# ProPrj_cheap-board-max-10_2026-05-07.net
KiCad netlist of a schematic drawn in EasyEDA Pro
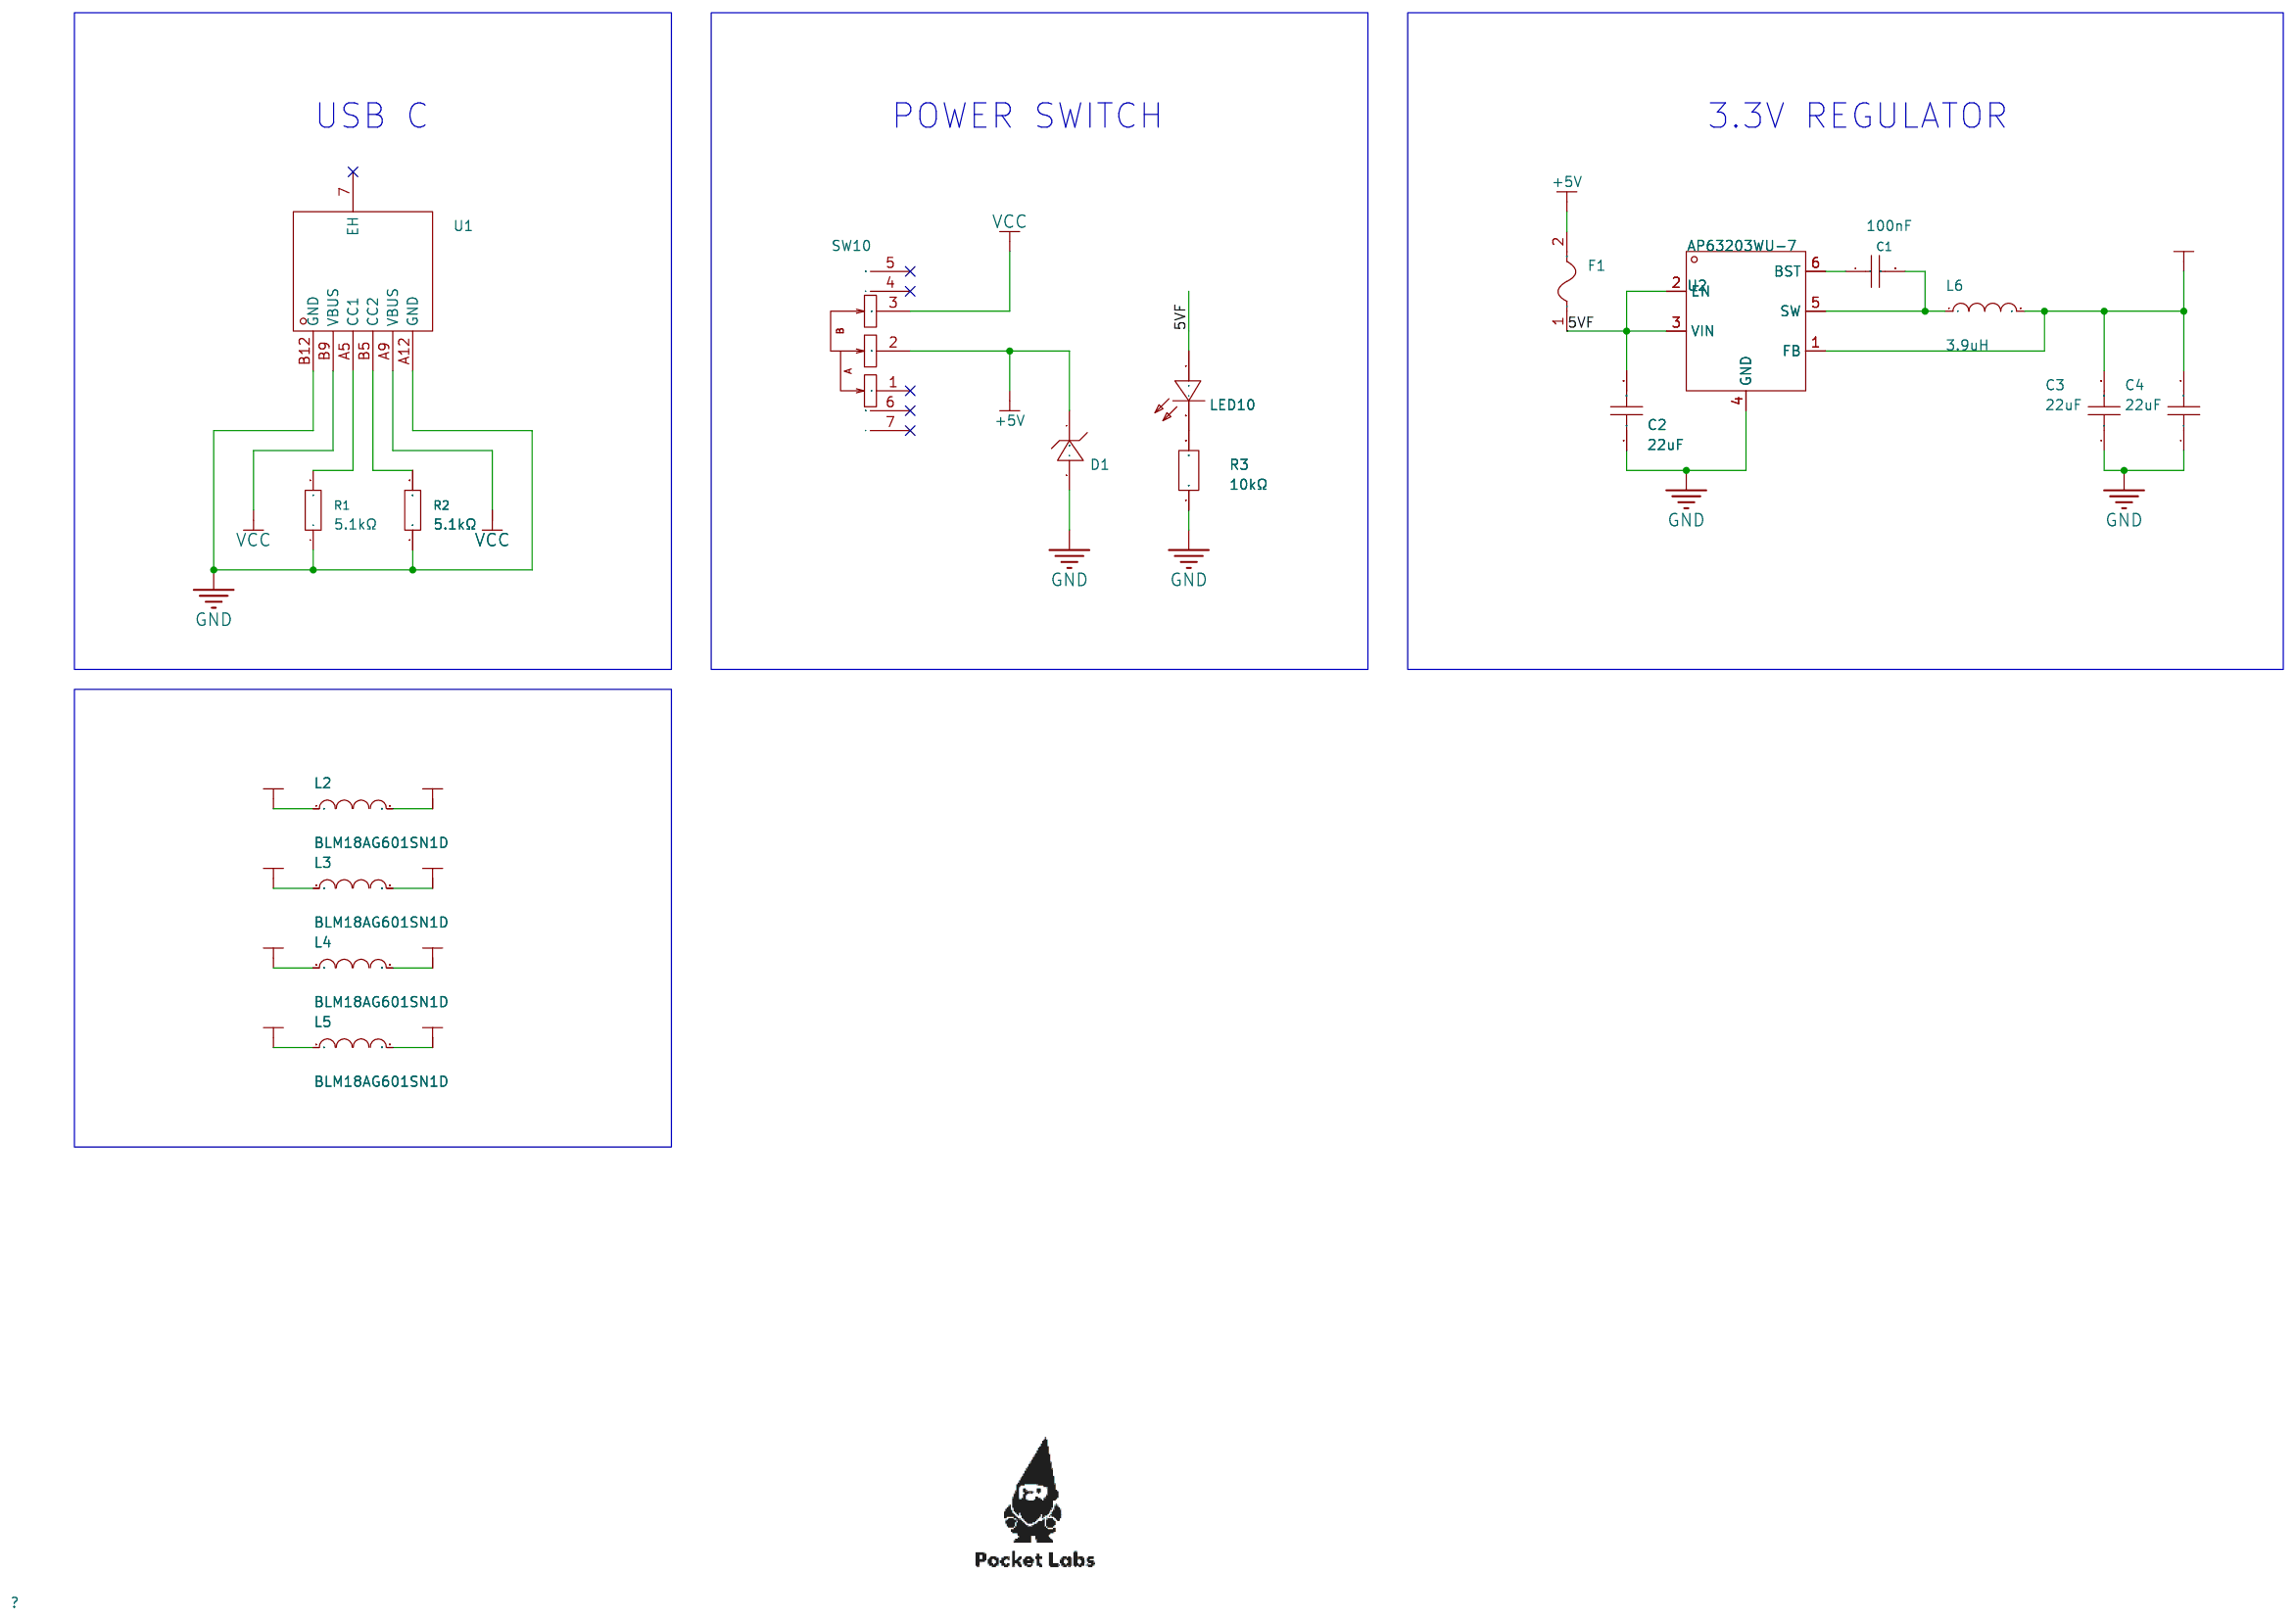
[diagram p0: PWR]
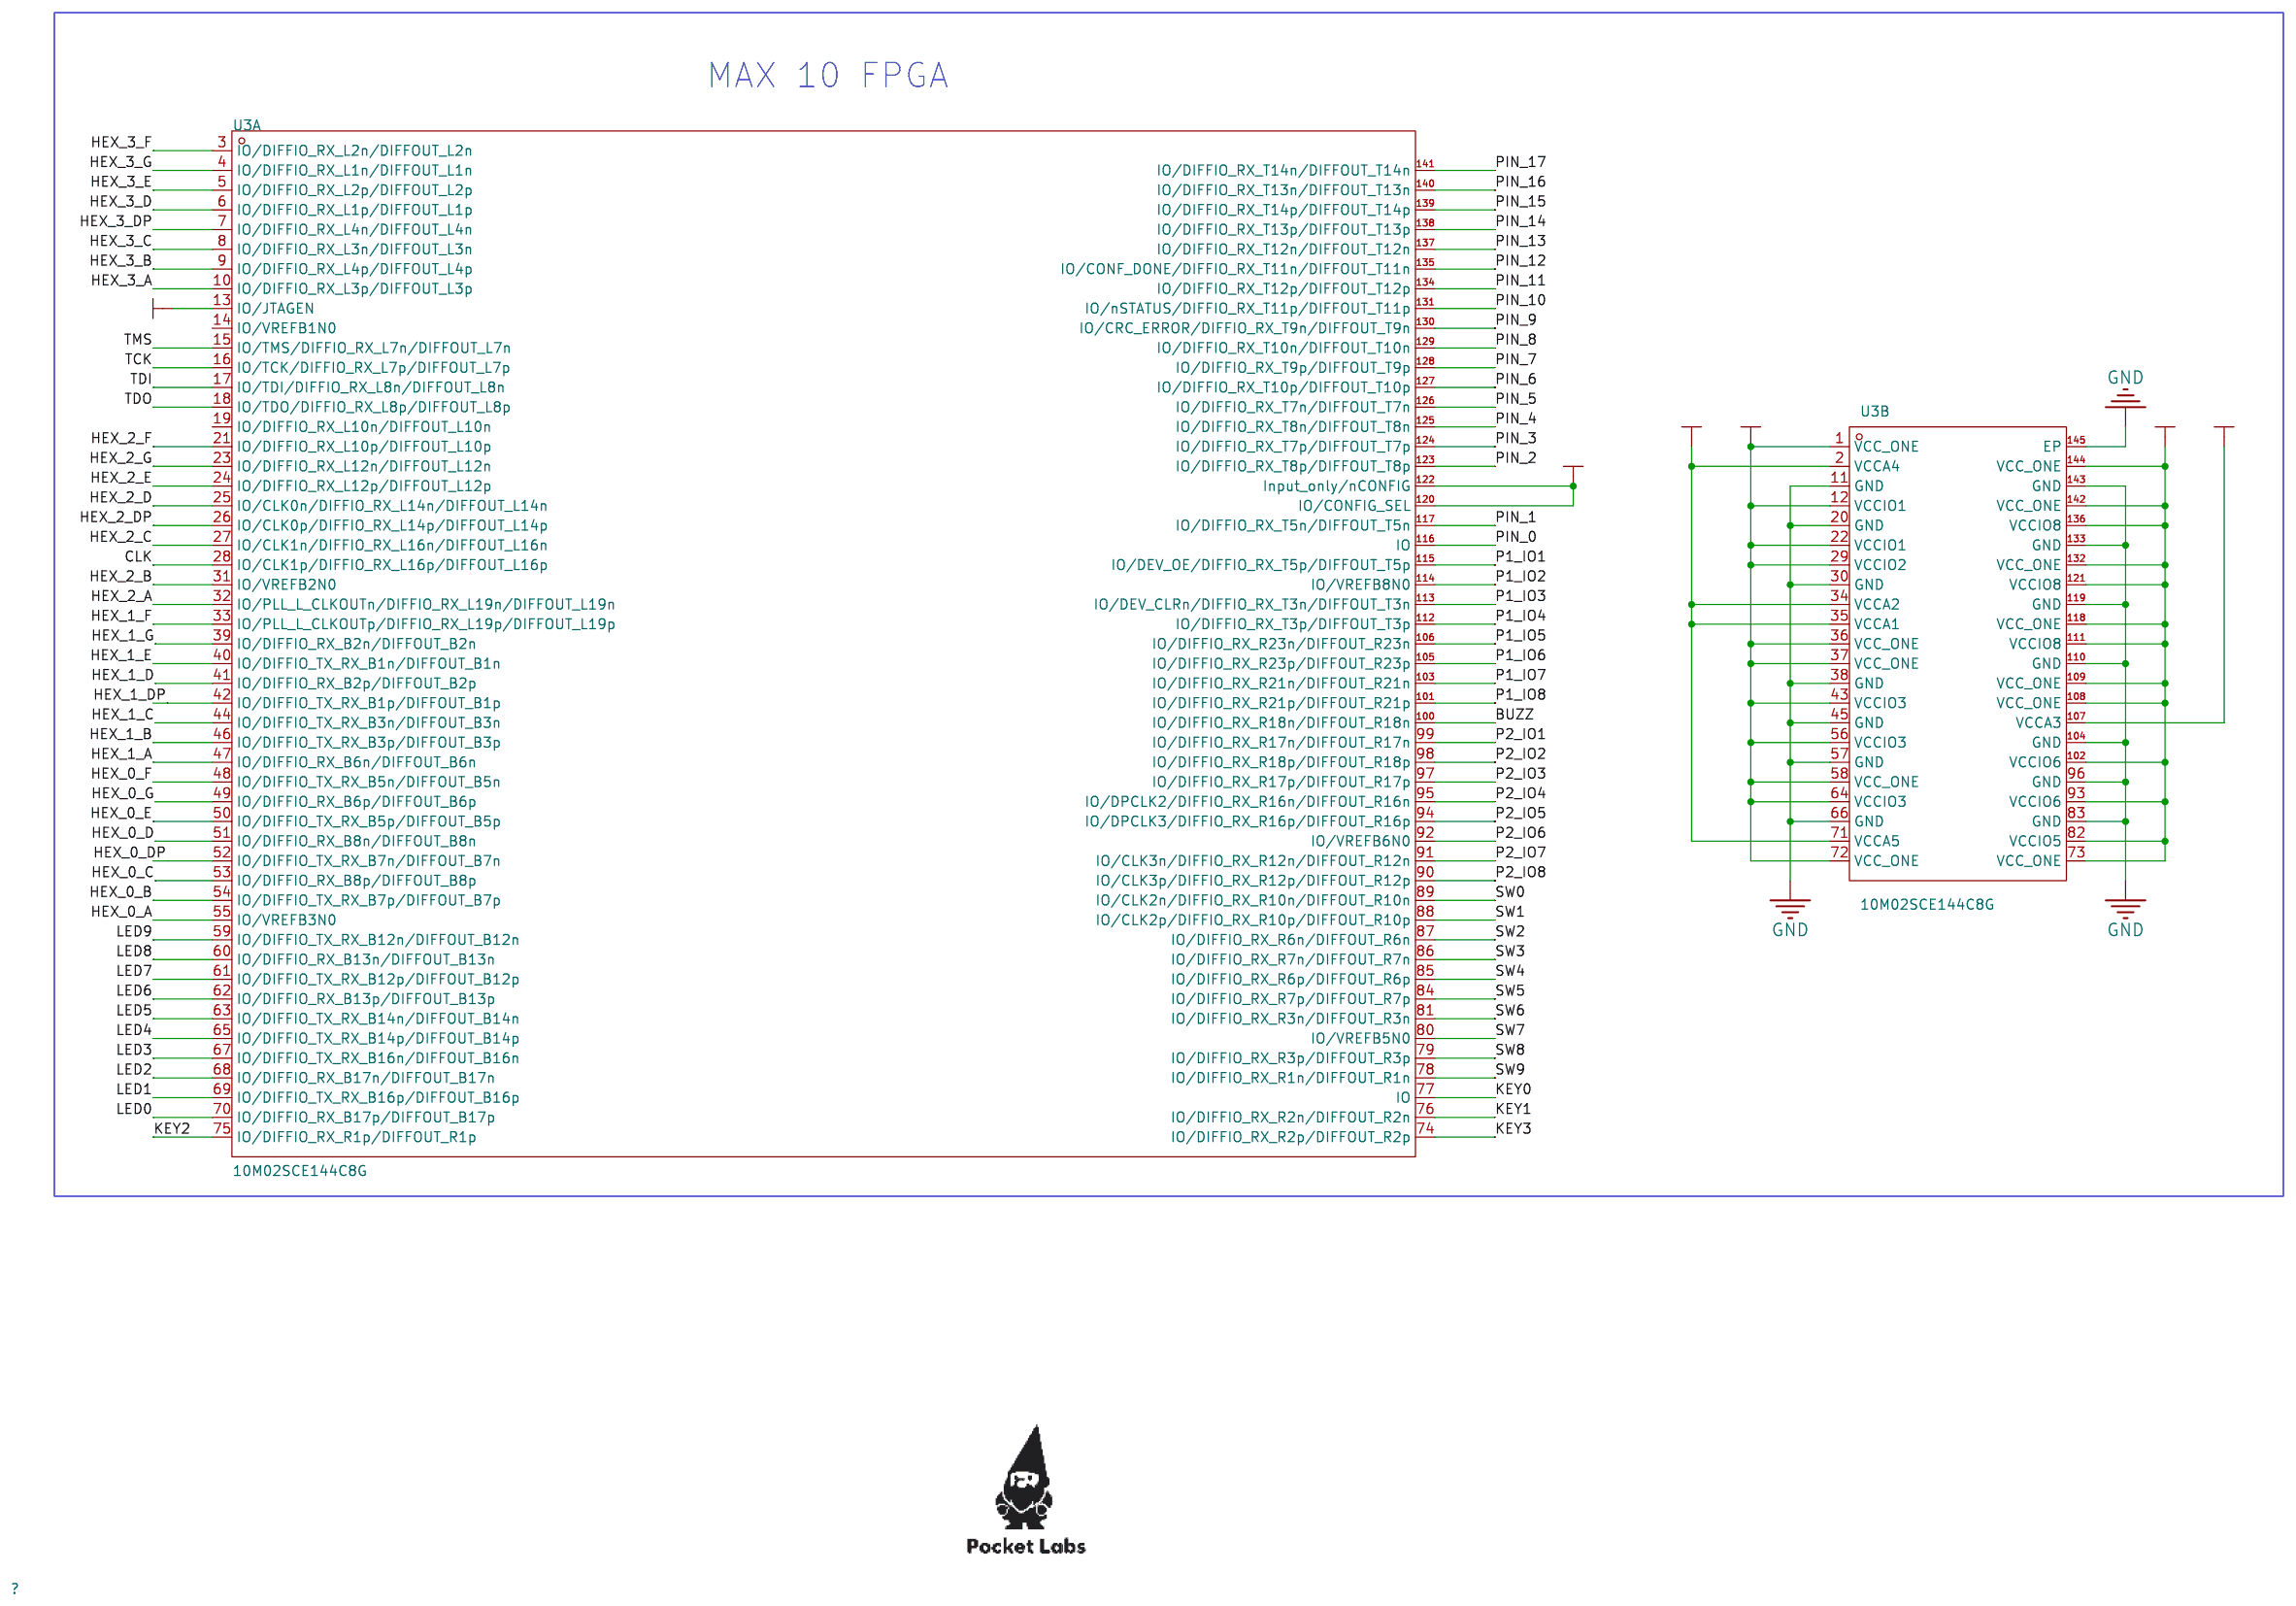
[diagram p1: MAX 10]
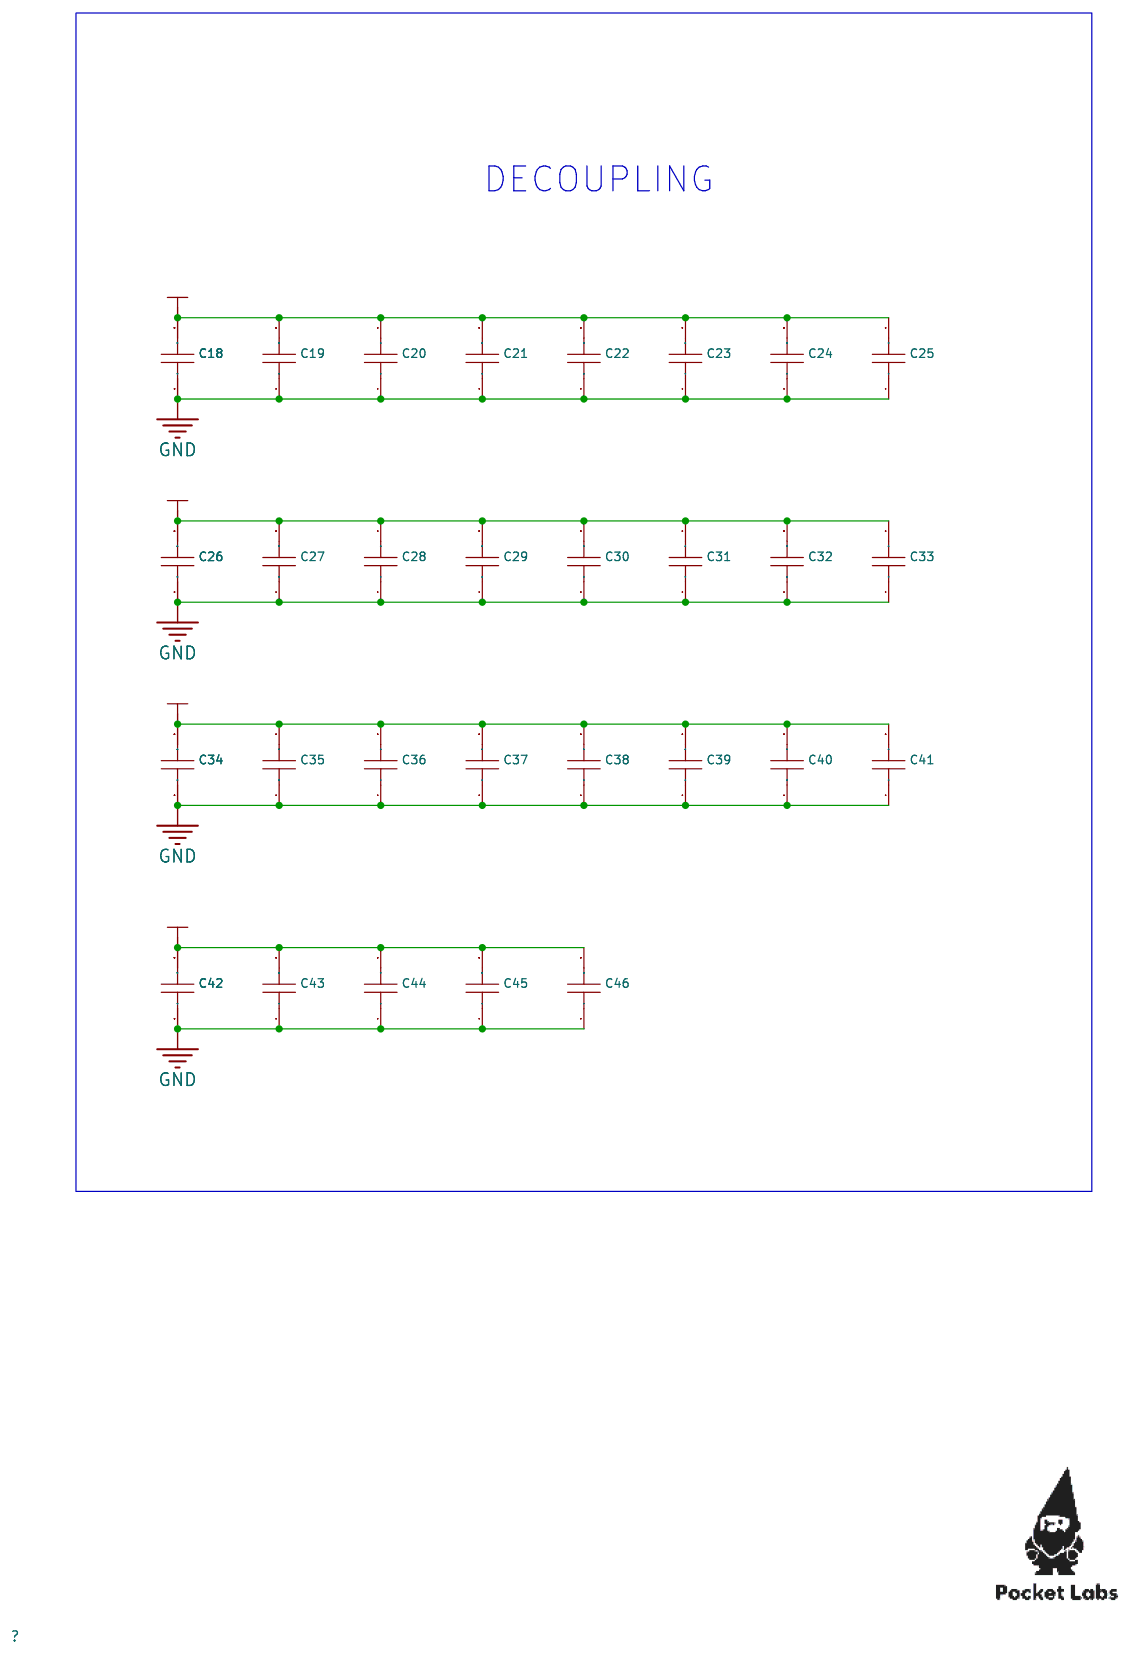
[diagram p2: DEC]
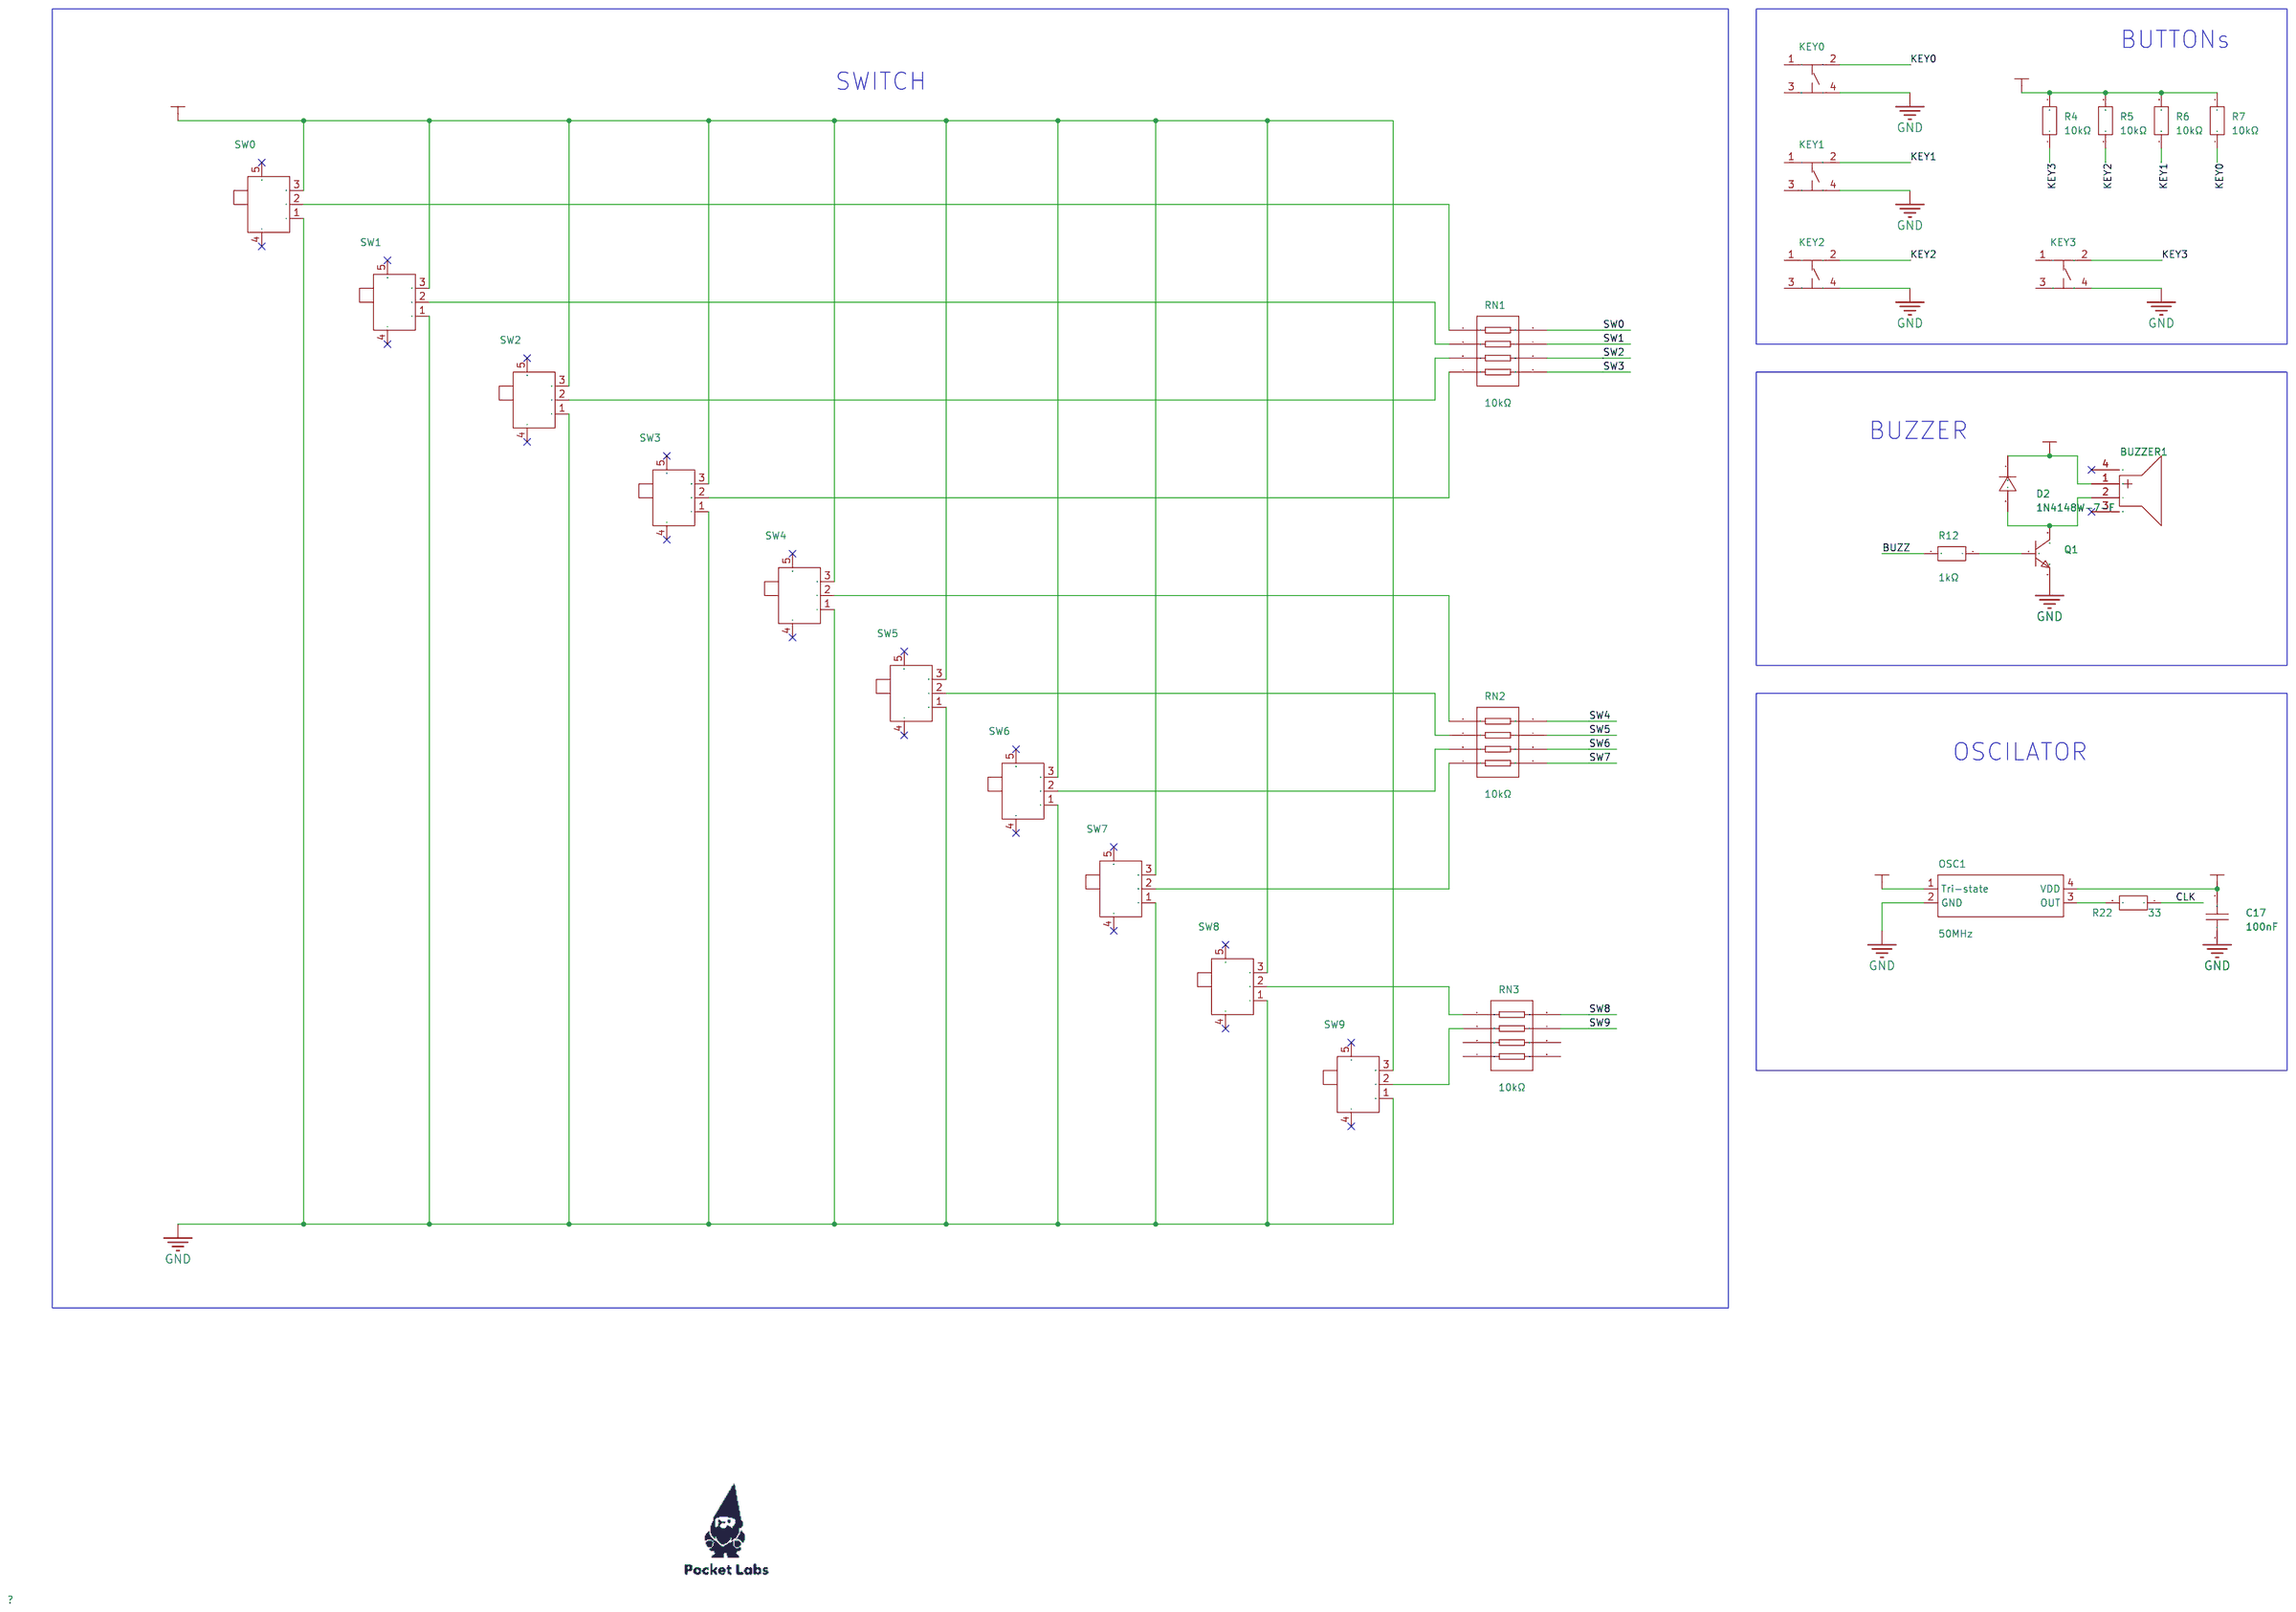
[diagram p3: PERIPHERALS]
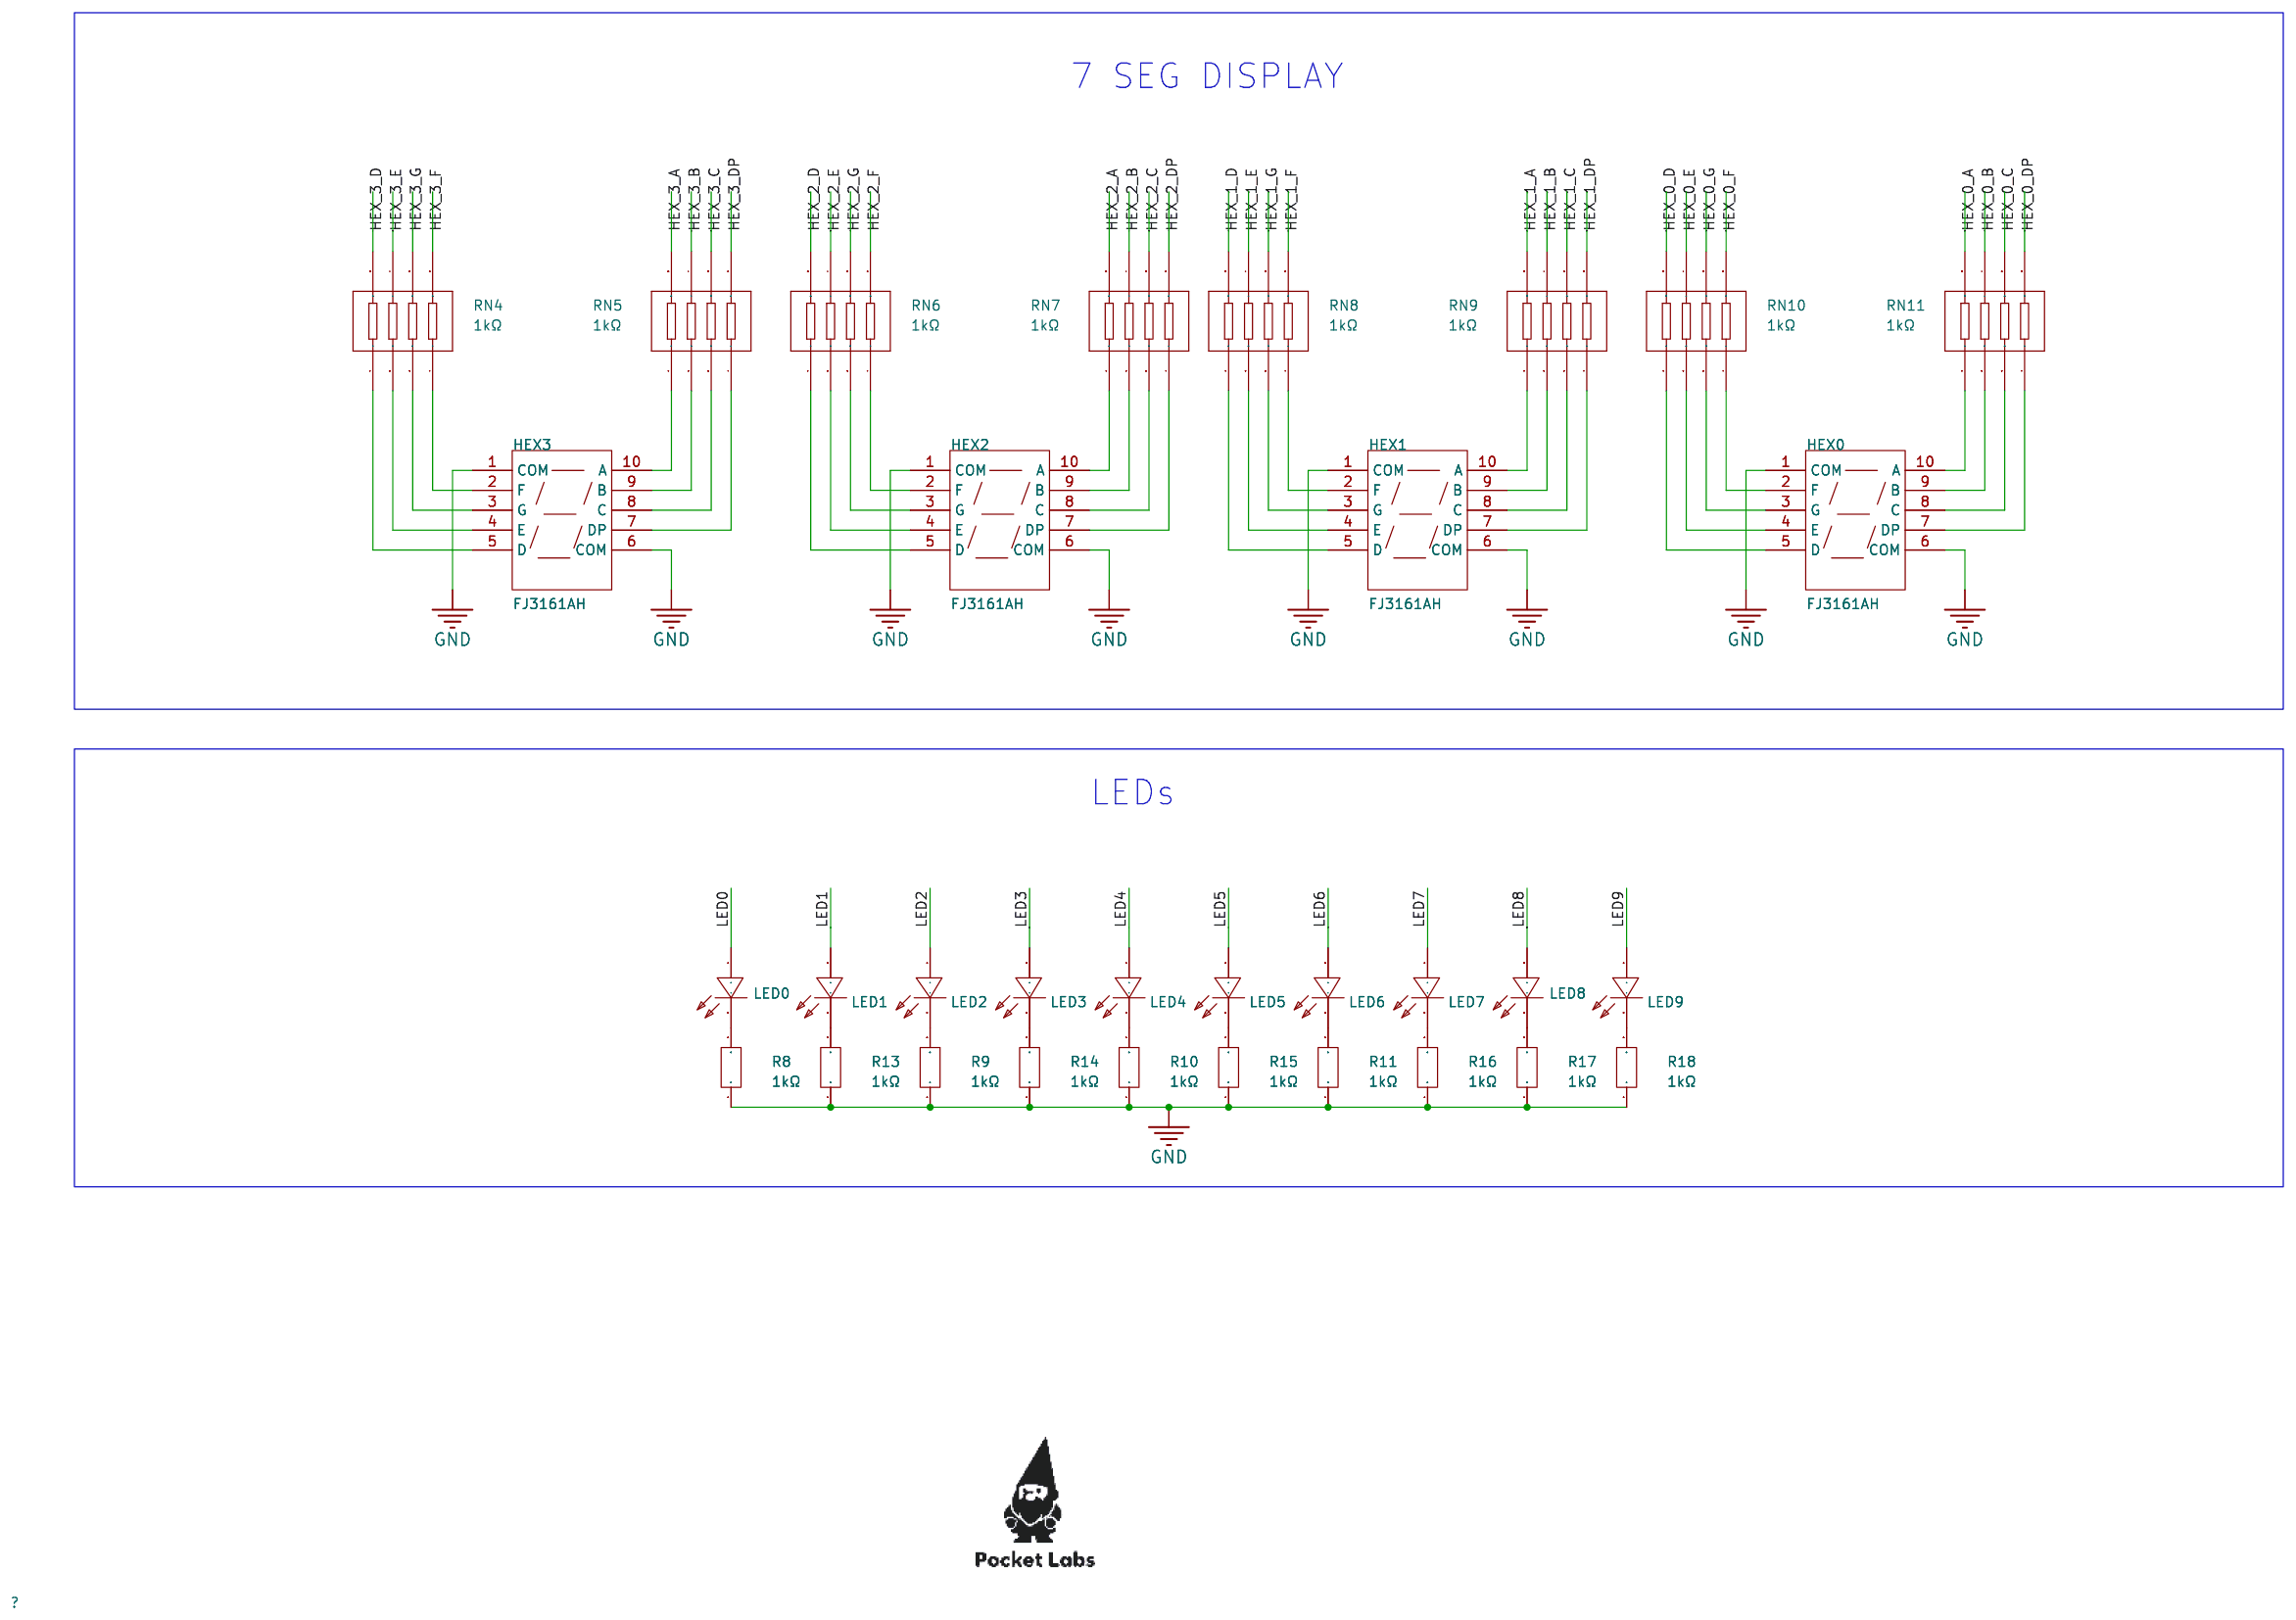
[diagram p4: LEDs]
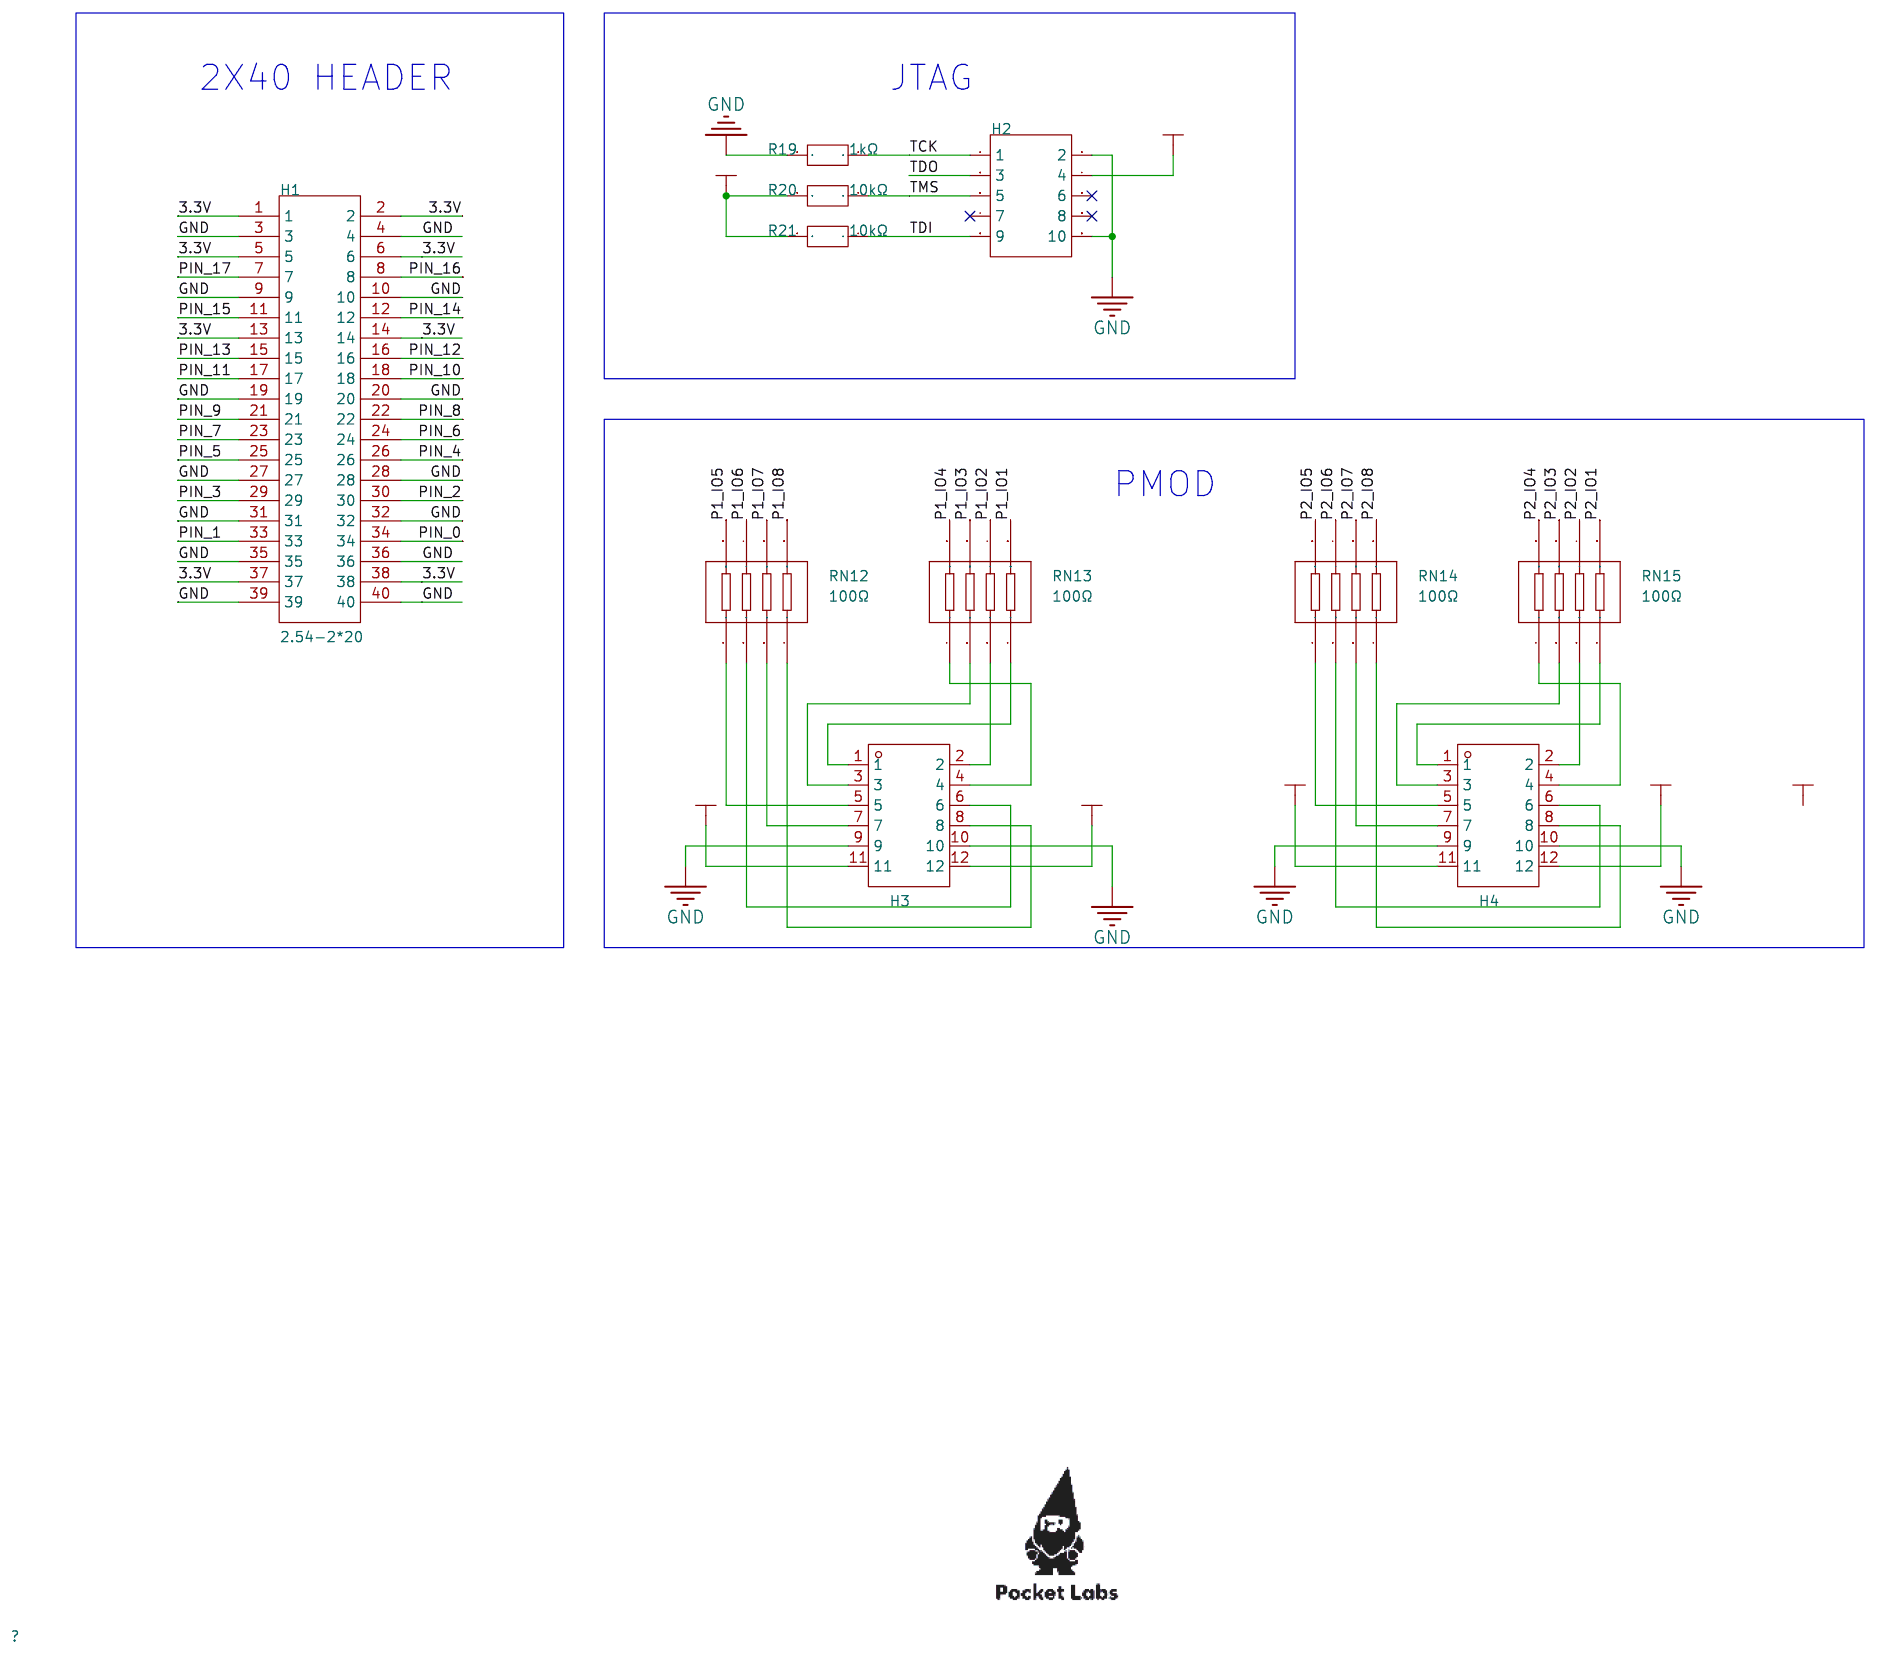
[diagram p5: CONN]

(export (version "E")
  (design (tool "Eeschema 10.0.6"))
  (components
    (comp (ref "C1")
      (value "100nF")
      (footprint "easyedapro:C0603")
      (description "Capacitance:100nF Tolerance:±10% Tolerance:±10% Voltage Rating:16V Temperature Coefficient:X7R")
      (fields
        (field (name "Manufacturer Part") "CL10B104KO8NNNC")
        (field (name "Manufacturer") "SAMSUNG(三星)")
      )
      (libsource (lib "easyedapro") (part "CL10B104KO8NNNC"))
    )
    (comp (ref "C2")
      (value "22uF")
      (footprint "easyedapro:C1206")
      (description "Capacitance:22uF Tolerance:±10% Tolerance:±10% Voltage Rating:16V Temperature Coefficient:X5R")
      (fields
        (field (name "Manufacturer Part") "CL31A226KOHNNNE")
        (field (name "Manufacturer") "SAMSUNG(三星)")
      )
      (libsource (lib "easyedapro") (part "CL31A226KOHNNNE"))
    )
    (comp (ref "C3")
      (value "22uF")
      (footprint "easyedapro:C1206")
      (description "Capacitance:22uF Tolerance:±10% Tolerance:±10% Voltage Rating:16V Temperature Coefficient:X5R")
      (fields
        (field (name "Manufacturer Part") "CL31A226KOHNNNE")
        (field (name "Manufacturer") "SAMSUNG(三星)")
      )
      (libsource (lib "easyedapro") (part "CL31A226KOHNNNE"))
    )
    (comp (ref "C4")
      (value "22uF")
      (footprint "easyedapro:C1206")
      (description "Capacitance:22uF Tolerance:±10% Tolerance:±10% Voltage Rating:16V Temperature Coefficient:X5R")
      (fields
        (field (name "Manufacturer Part") "CL31A226KOHNNNE")
        (field (name "Manufacturer") "SAMSUNG(三星)")
      )
      (libsource (lib "easyedapro") (part "CL31A226KOHNNNE"))
    )
    (comp (ref "D1")
      (value "SMF5.0A")
      (footprint "easyedapro:SOD-123FL_L2.7-W1.8-LS3.8-RD")
      (fields (field (name "Manufacturer") "MDD(辰达半导体)"))
      (libsource (lib "easyedapro") (part "SMF5.0A_C193402"))
    )
    (comp (ref "F1")
      (value "MF-MSMF050-2")
      (footprint "easyedapro:F1812")
      (fields (field (name "Manufacturer") "BOURNS"))
      (libsource (lib "easyedapro") (part "MF-MSMF050-2"))
    )
    (comp (ref "L2")
      (value "BLM18AG601SN1D")
      (footprint "easyedapro:L0603")
      (fields (field (name "Manufacturer") "muRata(村田)"))
      (libsource (lib "easyedapro") (part "BLM18AG601SN1D"))
    )
    (comp (ref "L3")
      (value "BLM18AG601SN1D")
      (footprint "easyedapro:L0603")
      (fields (field (name "Manufacturer") "muRata(村田)"))
      (libsource (lib "easyedapro") (part "BLM18AG601SN1D"))
    )
    (comp (ref "L4")
      (value "BLM18AG601SN1D")
      (footprint "easyedapro:L0603")
      (fields (field (name "Manufacturer") "muRata(村田)"))
      (libsource (lib "easyedapro") (part "BLM18AG601SN1D"))
    )
    (comp (ref "L5")
      (value "BLM18AG601SN1D")
      (footprint "easyedapro:L0603")
      (fields (field (name "Manufacturer") "muRata(村田)"))
      (libsource (lib "easyedapro") (part "BLM18AG601SN1D"))
    )
    (comp (ref "L6")
      (value "3.9uH")
      (footprint "easyedapro:IND-SMD_TNR4030S-3R9MTF")
      (fields (field (name "Manufacturer Part") "TNR4030S-3R9MTF") (field (name "Manufacturer") "APV(爱普微)"))
      (libsource (lib "easyedapro") (part "TNR4030S-3R9MTF"))
    )
    (comp (ref "LED10")
      (value "YLED0603R")
      (footprint "easyedapro:LED0805-R-RD")
      (fields (field (name "Manufacturer") "YONGYUTAI(永裕泰)"))
      (libsource (lib "easyedapro") (part "FC-2012HRK-620D"))
    )
    (comp (ref "R1")
      (value "5.1kΩ")
      (footprint "easyedapro:R0603")
      (fields (field (name "Manufacturer Part") "RMC06035.1K1%N") (field (name "Manufacturer") "Tyohm(幸亚电阻)"))
      (libsource (lib "easyedapro") (part "RMC06035.1K1%N"))
    )
    (comp (ref "R2")
      (value "5.1kΩ")
      (footprint "easyedapro:R0603")
      (fields (field (name "Manufacturer Part") "RMC06035.1K1%N") (field (name "Manufacturer") "Tyohm(幸亚电阻)"))
      (libsource (lib "easyedapro") (part "RMC06035.1K1%N"))
    )
    (comp (ref "R3")
      (value "10kΩ")
      (fields (field (name "Manufacturer Part") "RC0603FR-071KL") (field (name "Manufacturer") "YAGEO(国巨)"))
      (libsource (lib "easyedapro") (part "SC1206J1500F8ANRH"))
    )
    (comp (ref "SW10")
      (value "MK-12C02-G020")
      (fields (field (name "Manufacturer") "G-Switch(品赞)"))
      (libsource (lib "easyedapro") (part "MK-12C02-G015"))
    )
    (comp (ref "U1")
      (value "USB-TYPE-C-009")
      (footprint "easyedapro:TYPE-C-SMD_TYPE-C-6P")
      (fields (field (name "Manufacturer") "DEALON(德艺隆)"))
      (libsource (lib "easyedapro") (part "USB-TYPE-C-009"))
    )
    (comp (ref "U2")
      (value "AP63203WU-7")
      (footprint "easyedapro:TSOT-26_L2.9-W1.6-P0.95-LS2.8-BL")
      (fields (field (name "Manufacturer") "DIODES(美台)"))
      (libsource (lib "easyedapro") (part "AP63203WU-7"))
    )
    (comp (ref "U3")
      (value "10M02SCE144C8G")
      (footprint "easyedapro:EQFP-144_L20.0-W20.0-P0.50-LS22.0-BL-EP4.0")
      (fields (field (name "Manufacturer") "Intel/Altera"))
      (libsource (lib "easyedapro") (part "10M02SCE144C8G"))
    )
    (comp (ref "C18")
      (value "100nF")
      (footprint "easyedapro:C0402")
      (fields
        (field (name "Manufacturer Part") "CC0402KRX7R7BB104")
        (field (name "Manufacturer") "YAGEO(国巨)")
      )
      (libsource (lib "easyedapro") (part "CC0402KRX7R7BB104"))
    )
    (comp (ref "C19")
      (value "100nF")
      (footprint "easyedapro:C0402")
      (fields
        (field (name "Manufacturer Part") "CC0402KRX7R7BB104")
        (field (name "Manufacturer") "YAGEO(国巨)")
      )
      (libsource (lib "easyedapro") (part "CC0402KRX7R7BB104"))
    )
    (comp (ref "C20")
      (value "100nF")
      (footprint "easyedapro:C0402")
      (fields
        (field (name "Manufacturer Part") "CC0402KRX7R7BB104")
        (field (name "Manufacturer") "YAGEO(国巨)")
      )
      (libsource (lib "easyedapro") (part "CC0402KRX7R7BB104"))
    )
    (comp (ref "C21")
      (value "100nF")
      (footprint "easyedapro:C0402")
      (fields
        (field (name "Manufacturer Part") "CC0402KRX7R7BB104")
        (field (name "Manufacturer") "YAGEO(国巨)")
      )
      (libsource (lib "easyedapro") (part "CC0402KRX7R7BB104"))
    )
    (comp (ref "C22")
      (value "100nF")
      (footprint "easyedapro:C0402")
      (fields
        (field (name "Manufacturer Part") "CC0402KRX7R7BB104")
        (field (name "Manufacturer") "YAGEO(国巨)")
      )
      (libsource (lib "easyedapro") (part "CC0402KRX7R7BB104"))
    )
    (comp (ref "C23")
      (value "100nF")
      (footprint "easyedapro:C0402")
      (fields
        (field (name "Manufacturer Part") "CC0402KRX7R7BB104")
        (field (name "Manufacturer") "YAGEO(国巨)")
      )
      (libsource (lib "easyedapro") (part "CC0402KRX7R7BB104"))
    )
    (comp (ref "C24")
      (value "100nF")
      (footprint "easyedapro:C0402")
      (fields
        (field (name "Manufacturer Part") "CC0402KRX7R7BB104")
        (field (name "Manufacturer") "YAGEO(国巨)")
      )
      (libsource (lib "easyedapro") (part "CC0402KRX7R7BB104"))
    )
    (comp (ref "C25")
      (value "100nF")
      (footprint "easyedapro:C0402")
      (fields
        (field (name "Manufacturer Part") "CC0402KRX7R7BB104")
        (field (name "Manufacturer") "YAGEO(国巨)")
      )
      (libsource (lib "easyedapro") (part "CC0402KRX7R7BB104"))
    )
    (comp (ref "C26")
      (value "100nF")
      (footprint "easyedapro:C0402")
      (fields
        (field (name "Manufacturer Part") "CC0402KRX7R7BB104")
        (field (name "Manufacturer") "YAGEO(国巨)")
      )
      (libsource (lib "easyedapro") (part "CC0402KRX7R7BB104"))
    )
    (comp (ref "C27")
      (value "100nF")
      (footprint "easyedapro:C0402")
      (fields
        (field (name "Manufacturer Part") "CC0402KRX7R7BB104")
        (field (name "Manufacturer") "YAGEO(国巨)")
      )
      (libsource (lib "easyedapro") (part "CC0402KRX7R7BB104"))
    )
    (comp (ref "C28")
      (value "100nF")
      (footprint "easyedapro:C0402")
      (fields
        (field (name "Manufacturer Part") "CC0402KRX7R7BB104")
        (field (name "Manufacturer") "YAGEO(国巨)")
      )
      (libsource (lib "easyedapro") (part "CC0402KRX7R7BB104"))
    )
    (comp (ref "C29")
      (value "100nF")
      (footprint "easyedapro:C0402")
      (fields
        (field (name "Manufacturer Part") "CC0402KRX7R7BB104")
        (field (name "Manufacturer") "YAGEO(国巨)")
      )
      (libsource (lib "easyedapro") (part "CC0402KRX7R7BB104"))
    )
    (comp (ref "C30")
      (value "100nF")
      (footprint "easyedapro:C0402")
      (fields
        (field (name "Manufacturer Part") "CC0402KRX7R7BB104")
        (field (name "Manufacturer") "YAGEO(国巨)")
      )
      (libsource (lib "easyedapro") (part "CC0402KRX7R7BB104"))
    )
    (comp (ref "C31")
      (value "100nF")
      (footprint "easyedapro:C0402")
      (fields
        (field (name "Manufacturer Part") "CC0402KRX7R7BB104")
        (field (name "Manufacturer") "YAGEO(国巨)")
      )
      (libsource (lib "easyedapro") (part "CC0402KRX7R7BB104"))
    )
    (comp (ref "C32")
      (value "100nF")
      (footprint "easyedapro:C0402")
      (fields
        (field (name "Manufacturer Part") "CC0402KRX7R7BB104")
        (field (name "Manufacturer") "YAGEO(国巨)")
      )
      (libsource (lib "easyedapro") (part "CC0402KRX7R7BB104"))
    )
    (comp (ref "C33")
      (value "100nF")
      (footprint "easyedapro:C0402")
      (fields
        (field (name "Manufacturer Part") "CC0402KRX7R7BB104")
        (field (name "Manufacturer") "YAGEO(国巨)")
      )
      (libsource (lib "easyedapro") (part "CC0402KRX7R7BB104"))
    )
    (comp (ref "C34")
      (value "100nF")
      (footprint "easyedapro:C0402")
      (fields
        (field (name "Manufacturer Part") "CC0402KRX7R7BB104")
        (field (name "Manufacturer") "YAGEO(国巨)")
      )
      (libsource (lib "easyedapro") (part "CC0402KRX7R7BB104"))
    )
    (comp (ref "C35")
      (value "100nF")
      (footprint "easyedapro:C0402")
      (fields
        (field (name "Manufacturer Part") "CC0402KRX7R7BB104")
        (field (name "Manufacturer") "YAGEO(国巨)")
      )
      (libsource (lib "easyedapro") (part "CC0402KRX7R7BB104"))
    )
    (comp (ref "C36")
      (value "100nF")
      (footprint "easyedapro:C0402")
      (fields
        (field (name "Manufacturer Part") "CC0402KRX7R7BB104")
        (field (name "Manufacturer") "YAGEO(国巨)")
      )
      (libsource (lib "easyedapro") (part "CC0402KRX7R7BB104"))
    )
    (comp (ref "C37")
      (value "100nF")
      (footprint "easyedapro:C0402")
      (fields
        (field (name "Manufacturer Part") "CC0402KRX7R7BB104")
        (field (name "Manufacturer") "YAGEO(国巨)")
      )
      (libsource (lib "easyedapro") (part "CC0402KRX7R7BB104"))
    )
    (comp (ref "C38")
      (value "100nF")
      (footprint "easyedapro:C0402")
      (fields
        (field (name "Manufacturer Part") "CC0402KRX7R7BB104")
        (field (name "Manufacturer") "YAGEO(国巨)")
      )
      (libsource (lib "easyedapro") (part "CC0402KRX7R7BB104"))
    )
    (comp (ref "C39")
      (value "100nF")
      (footprint "easyedapro:C0402")
      (fields
        (field (name "Manufacturer Part") "CC0402KRX7R7BB104")
        (field (name "Manufacturer") "YAGEO(国巨)")
      )
      (libsource (lib "easyedapro") (part "CC0402KRX7R7BB104"))
    )
    (comp (ref "C40")
      (value "100nF")
      (footprint "easyedapro:C0402")
      (fields
        (field (name "Manufacturer Part") "CC0402KRX7R7BB104")
        (field (name "Manufacturer") "YAGEO(国巨)")
      )
      (libsource (lib "easyedapro") (part "CC0402KRX7R7BB104"))
    )
    (comp (ref "C41")
      (value "100nF")
      (footprint "easyedapro:C0402")
      (fields
        (field (name "Manufacturer Part") "CC0402KRX7R7BB104")
        (field (name "Manufacturer") "YAGEO(国巨)")
      )
      (libsource (lib "easyedapro") (part "CC0402KRX7R7BB104"))
    )
    (comp (ref "C42")
      (value "100nF")
      (footprint "easyedapro:C0402")
      (fields
        (field (name "Manufacturer Part") "CC0402KRX7R7BB104")
        (field (name "Manufacturer") "YAGEO(国巨)")
      )
      (libsource (lib "easyedapro") (part "CC0402KRX7R7BB104"))
    )
    (comp (ref "C43")
      (value "100nF")
      (footprint "easyedapro:C0402")
      (fields
        (field (name "Manufacturer Part") "CC0402KRX7R7BB104")
        (field (name "Manufacturer") "YAGEO(国巨)")
      )
      (libsource (lib "easyedapro") (part "CC0402KRX7R7BB104"))
    )
    (comp (ref "C44")
      (value "100nF")
      (footprint "easyedapro:C0402")
      (fields
        (field (name "Manufacturer Part") "CC0402KRX7R7BB104")
        (field (name "Manufacturer") "YAGEO(国巨)")
      )
      (libsource (lib "easyedapro") (part "CC0402KRX7R7BB104"))
    )
    (comp (ref "C45")
      (value "100nF")
      (footprint "easyedapro:C0402")
      (fields
        (field (name "Manufacturer Part") "CC0402KRX7R7BB104")
        (field (name "Manufacturer") "YAGEO(国巨)")
      )
      (libsource (lib "easyedapro") (part "CC0402KRX7R7BB104"))
    )
    (comp (ref "C46")
      (value "100nF")
      (footprint "easyedapro:C0402")
      (fields
        (field (name "Manufacturer Part") "CC0402KRX7R7BB104")
        (field (name "Manufacturer") "YAGEO(国巨)")
      )
      (libsource (lib "easyedapro") (part "CC0402KRX7R7BB104"))
    )
    (comp (ref "BUZZER1")
      (value "2.7kHz")
      (footprint "easyedapro:BUZ-SMD_4P-L7.5-W7.5-P7.59-TL")
      (fields (field (name "Manufacturer Part") "MLT-7525") (field (name "Manufacturer") "华能"))
      (libsource (lib "easyedapro") (part "MLT-7525"))
    )
    (comp (ref "C17")
      (value "100nF")
      (footprint "easyedapro:C0603")
      (description "Capacitance:100nF Tolerance:±10% Tolerance:±10% Voltage Rating:50V Temperature Coefficient:X7R")
      (fields
        (field (name "Manufacturer Part") "CC0603KRX7R9BB104")
        (field (name "Manufacturer") "YAGEO(国巨)")
      )
      (libsource (lib "easyedapro") (part "CC0603KRX7R9BB104"))
    )
    (comp (ref "D2")
      (value "1N4148W-7-F")
      (footprint "easyedapro:SOD-123_L2.7-W1.6-LS3.7-RD-1")
      (fields (field (name "Manufacturer") "DIODES(美台)"))
      (libsource (lib "easyedapro") (part "1N4148W-7-F"))
    )
    (comp (ref "KEY0")
      (value "KH-6X6X6H-STM")
      (footprint "easyedapro:SW-SMD_4P-L6.0-W6.0-P4.50-LS9.0_KH-6X6X6H-STM")
      (fields (field (name "Manufacturer") "kinghelm(金航标)"))
      (libsource (lib "easyedapro") (part "KH-6X6X6H-STM"))
    )
    (comp (ref "KEY1")
      (value "KH-6X6X6H-STM")
      (footprint "easyedapro:SW-SMD_4P-L6.0-W6.0-P4.50-LS9.0_KH-6X6X6H-STM")
      (fields (field (name "Manufacturer") "kinghelm(金航标)"))
      (libsource (lib "easyedapro") (part "KH-6X6X6H-STM"))
    )
    (comp (ref "KEY2")
      (value "KH-6X6X6H-STM")
      (footprint "easyedapro:SW-SMD_4P-L6.0-W6.0-P4.50-LS9.0_KH-6X6X6H-STM")
      (fields (field (name "Manufacturer") "kinghelm(金航标)"))
      (libsource (lib "easyedapro") (part "KH-6X6X6H-STM"))
    )
    (comp (ref "KEY3")
      (value "KH-6X6X6H-STM")
      (footprint "easyedapro:SW-SMD_4P-L6.0-W6.0-P4.50-LS9.0_KH-6X6X6H-STM")
      (fields (field (name "Manufacturer") "kinghelm(金航标)"))
      (libsource (lib "easyedapro") (part "KH-6X6X6H-STM"))
    )
    (comp (ref "OSC1")
      (value "50MHz")
      (footprint "easyedapro:OSC-SMD_4P-L3.2-W2.5-BL")
      (fields
        (field (name "Manufacturer Part") "OT2EL4C4JI-111OLP-50M")
        (field (name "Manufacturer") "YXC(扬兴晶振)")
      )
      (libsource (lib "easyedapro") (part "OT2EL4C4JI-111OLP-50M"))
    )
    (comp (ref "Q1")
      (value "MMBT3904LT1G")
      (footprint "easyedapro:SOT-23-3_L2.9-W1.6-P1.90-LS2.8-BR")
      (fields (field (name "Manufacturer") "onsemi(安森美)"))
      (libsource (lib "easyedapro") (part "MMBT3904LT1G"))
    )
    (comp (ref "R4")
      (value "10kΩ")
      (fields (field (name "Manufacturer Part") "RC0603FR-071KL") (field (name "Manufacturer") "YAGEO(国巨)"))
      (libsource (lib "easyedapro") (part "SC1206J1500F8ANRH"))
    )
    (comp (ref "R5")
      (value "10kΩ")
      (fields (field (name "Manufacturer Part") "RC0603FR-071KL") (field (name "Manufacturer") "YAGEO(国巨)"))
      (libsource (lib "easyedapro") (part "SC1206J1500F8ANRH"))
    )
    (comp (ref "R6")
      (value "10kΩ")
      (fields (field (name "Manufacturer Part") "RC0603FR-071KL") (field (name "Manufacturer") "YAGEO(国巨)"))
      (libsource (lib "easyedapro") (part "SC1206J1500F8ANRH"))
    )
    (comp (ref "R7")
      (value "10kΩ")
      (fields (field (name "Manufacturer Part") "RC0603FR-071KL") (field (name "Manufacturer") "YAGEO(国巨)"))
      (libsource (lib "easyedapro") (part "SC1206J1500F8ANRH"))
    )
    (comp (ref "R12")
      (value "1kΩ")
      (fields (field (name "Manufacturer Part") "RC0603FR-071KL") (field (name "Manufacturer") "YAGEO(国巨)"))
      (libsource (lib "easyedapro") (part "SC1206J1500F8ANRH"))
    )
    (comp (ref "R22")
      (value "33")
      (fields (field (name "Manufacturer Part") "RC0603FR-071KL") (field (name "Manufacturer") "YAGEO(国巨)"))
      (libsource (lib "easyedapro") (part "SC1206J1500F8ANRH"))
    )
    (comp (ref "RN1")
      (value "10kΩ")
      (footprint "easyedapro:RES-ARRAY-SMD_0603-8P-L3.2-W1.6-BL")
      (fields
        (field (name "Manufacturer Part") "4D03WGJ0103T5E")
        (field (name "Manufacturer") "UNI-ROYAL(厚声)")
      )
      (libsource (lib "easyedapro") (part "4D03WGJ0103T5E"))
    )
    (comp (ref "RN2")
      (value "10kΩ")
      (footprint "easyedapro:RES-ARRAY-SMD_0603-8P-L3.2-W1.6-BL")
      (fields
        (field (name "Manufacturer Part") "4D03WGJ0103T5E")
        (field (name "Manufacturer") "UNI-ROYAL(厚声)")
      )
      (libsource (lib "easyedapro") (part "4D03WGJ0103T5E"))
    )
    (comp (ref "RN3")
      (value "10kΩ")
      (footprint "easyedapro:RES-ARRAY-SMD_0603-8P-L3.2-W1.6-BL")
      (fields
        (field (name "Manufacturer Part") "4D03WGJ0103T5E")
        (field (name "Manufacturer") "UNI-ROYAL(厚声)")
      )
      (libsource (lib "easyedapro") (part "4D03WGJ0103T5E"))
    )
    (comp (ref "SW0")
      (value "SS12F44G4")
      (fields (field (name "Manufacturer") "SHOU HAN(首韩)"))
      (libsource (lib "easyedapro") (part "SS12D07VG4 087"))
    )
    (comp (ref "SW1")
      (value "SS12F44G4")
      (fields (field (name "Manufacturer") "SHOU HAN(首韩)"))
      (libsource (lib "easyedapro") (part "SS12D07VG4 087"))
    )
    (comp (ref "SW2")
      (value "SS12F44G4")
      (fields (field (name "Manufacturer") "SHOU HAN(首韩)"))
      (libsource (lib "easyedapro") (part "SS12D07VG4 087"))
    )
    (comp (ref "SW3")
      (value "SS12F44G4")
      (fields (field (name "Manufacturer") "SHOU HAN(首韩)"))
      (libsource (lib "easyedapro") (part "SS12D07VG4 087"))
    )
    (comp (ref "SW4")
      (value "SS12F44G4")
      (fields (field (name "Manufacturer") "SHOU HAN(首韩)"))
      (libsource (lib "easyedapro") (part "SS12D07VG4 087"))
    )
    (comp (ref "SW5")
      (value "SS12F44G4")
      (fields (field (name "Manufacturer") "SHOU HAN(首韩)"))
      (libsource (lib "easyedapro") (part "SS12D07VG4 087"))
    )
    (comp (ref "SW6")
      (value "SS12F44G4")
      (fields (field (name "Manufacturer") "SHOU HAN(首韩)"))
      (libsource (lib "easyedapro") (part "SS12D07VG4 087"))
    )
    (comp (ref "SW7")
      (value "SS12F44G4")
      (fields (field (name "Manufacturer") "SHOU HAN(首韩)"))
      (libsource (lib "easyedapro") (part "SS12D07VG4 087"))
    )
    (comp (ref "SW8")
      (value "SS12F44G4")
      (fields (field (name "Manufacturer") "SHOU HAN(首韩)"))
      (libsource (lib "easyedapro") (part "SS12D07VG4 087"))
    )
    (comp (ref "SW9")
      (value "SS12F44G4")
      (fields (field (name "Manufacturer") "SHOU HAN(首韩)"))
      (libsource (lib "easyedapro") (part "SS12D07VG4 087"))
    )
    (comp (ref "HEX0")
      (value "FJ3161AH")
      (footprint "easyedapro:LED-SEG-TH_10P-L14.0-W7.5-P2.54-S5.08-TL")
      (description "Digit/Alpha Size(inch):0.36 Illumination Color:Red LED Polarity:Common Cathode")
      (fields (field (name "Manufacturer") "志浩"))
      (libsource (lib "easyedapro") (part "XL-DB3161SRBC"))
    )
    (comp (ref "HEX1")
      (value "FJ3161AH")
      (footprint "easyedapro:LED-SEG-TH_10P-L14.0-W7.5-P2.54-S5.08-TL")
      (description "Digit/Alpha Size(inch):0.36 Illumination Color:Red LED Polarity:Common Cathode")
      (fields (field (name "Manufacturer") "志浩"))
      (libsource (lib "easyedapro") (part "XL-DB3161SRBC"))
    )
    (comp (ref "HEX2")
      (value "FJ3161AH")
      (footprint "easyedapro:LED-SEG-TH_10P-L14.0-W7.5-P2.54-S5.08-TL")
      (description "Digit/Alpha Size(inch):0.36 Illumination Color:Red LED Polarity:Common Cathode")
      (fields (field (name "Manufacturer") "志浩"))
      (libsource (lib "easyedapro") (part "XL-DB3161SRBC"))
    )
    (comp (ref "HEX3")
      (value "FJ3161AH")
      (footprint "easyedapro:LED-SEG-TH_10P-L14.0-W7.5-P2.54-S5.08-TL")
      (description "Digit/Alpha Size(inch):0.36 Illumination Color:Red LED Polarity:Common Cathode")
      (fields (field (name "Manufacturer") "志浩"))
      (libsource (lib "easyedapro") (part "XL-DB3161SRBC"))
    )
    (comp (ref "LED0")
      (value "YLED0603R")
      (footprint "easyedapro:LED0805-R-RD")
      (fields (field (name "Manufacturer") "YONGYUTAI(永裕泰)"))
      (libsource (lib "easyedapro") (part "FC-2012HRK-620D"))
    )
    (comp (ref "LED1")
      (value "YLED0603R")
      (footprint "easyedapro:LED0805-R-RD")
      (fields (field (name "Manufacturer") "YONGYUTAI(永裕泰)"))
      (libsource (lib "easyedapro") (part "FC-2012HRK-620D"))
    )
    (comp (ref "LED2")
      (value "YLED0603R")
      (footprint "easyedapro:LED0805-R-RD")
      (fields (field (name "Manufacturer") "YONGYUTAI(永裕泰)"))
      (libsource (lib "easyedapro") (part "FC-2012HRK-620D"))
    )
    (comp (ref "LED3")
      (value "YLED0603R")
      (footprint "easyedapro:LED0805-R-RD")
      (fields (field (name "Manufacturer") "YONGYUTAI(永裕泰)"))
      (libsource (lib "easyedapro") (part "FC-2012HRK-620D"))
    )
    (comp (ref "LED4")
      (value "YLED0603R")
      (footprint "easyedapro:LED0805-R-RD")
      (fields (field (name "Manufacturer") "YONGYUTAI(永裕泰)"))
      (libsource (lib "easyedapro") (part "FC-2012HRK-620D"))
    )
    (comp (ref "LED5")
      (value "YLED0603R")
      (footprint "easyedapro:LED0805-R-RD")
      (fields (field (name "Manufacturer") "YONGYUTAI(永裕泰)"))
      (libsource (lib "easyedapro") (part "FC-2012HRK-620D"))
    )
    (comp (ref "LED6")
      (value "YLED0603R")
      (footprint "easyedapro:LED0805-R-RD")
      (fields (field (name "Manufacturer") "YONGYUTAI(永裕泰)"))
      (libsource (lib "easyedapro") (part "FC-2012HRK-620D"))
    )
    (comp (ref "LED7")
      (value "YLED0603R")
      (footprint "easyedapro:LED0805-R-RD")
      (fields (field (name "Manufacturer") "YONGYUTAI(永裕泰)"))
      (libsource (lib "easyedapro") (part "FC-2012HRK-620D"))
    )
    (comp (ref "LED8")
      (value "YLED0603R")
      (footprint "easyedapro:LED0805-R-RD")
      (fields (field (name "Manufacturer") "YONGYUTAI(永裕泰)"))
      (libsource (lib "easyedapro") (part "FC-2012HRK-620D"))
    )
    (comp (ref "LED9")
      (value "YLED0603R")
      (footprint "easyedapro:LED0805-R-RD")
      (fields (field (name "Manufacturer") "YONGYUTAI(永裕泰)"))
      (libsource (lib "easyedapro") (part "FC-2012HRK-620D"))
    )
    (comp (ref "R8")
      (value "1kΩ")
      (fields (field (name "Manufacturer Part") "RC0603FR-071KL") (field (name "Manufacturer") "YAGEO(国巨)"))
      (libsource (lib "easyedapro") (part "SC1206J1500F8ANRH"))
    )
    (comp (ref "R9")
      (value "1kΩ")
      (fields (field (name "Manufacturer Part") "RC0603FR-071KL") (field (name "Manufacturer") "YAGEO(国巨)"))
      (libsource (lib "easyedapro") (part "SC1206J1500F8ANRH"))
    )
    (comp (ref "R10")
      (value "1kΩ")
      (fields (field (name "Manufacturer Part") "RC0603FR-071KL") (field (name "Manufacturer") "YAGEO(国巨)"))
      (libsource (lib "easyedapro") (part "SC1206J1500F8ANRH"))
    )
    (comp (ref "R11")
      (value "1kΩ")
      (fields (field (name "Manufacturer Part") "RC0603FR-071KL") (field (name "Manufacturer") "YAGEO(国巨)"))
      (libsource (lib "easyedapro") (part "SC1206J1500F8ANRH"))
    )
    (comp (ref "R13")
      (value "1kΩ")
      (fields (field (name "Manufacturer Part") "RC0603FR-071KL") (field (name "Manufacturer") "YAGEO(国巨)"))
      (libsource (lib "easyedapro") (part "SC1206J1500F8ANRH"))
    )
    (comp (ref "R14")
      (value "1kΩ")
      (fields (field (name "Manufacturer Part") "RC0603FR-071KL") (field (name "Manufacturer") "YAGEO(国巨)"))
      (libsource (lib "easyedapro") (part "SC1206J1500F8ANRH"))
    )
    (comp (ref "R15")
      (value "1kΩ")
      (fields (field (name "Manufacturer Part") "RC0603FR-071KL") (field (name "Manufacturer") "YAGEO(国巨)"))
      (libsource (lib "easyedapro") (part "SC1206J1500F8ANRH"))
    )
    (comp (ref "R16")
      (value "1kΩ")
      (fields (field (name "Manufacturer Part") "RC0603FR-071KL") (field (name "Manufacturer") "YAGEO(国巨)"))
      (libsource (lib "easyedapro") (part "SC1206J1500F8ANRH"))
    )
    (comp (ref "R17")
      (value "1kΩ")
      (fields (field (name "Manufacturer Part") "RC0603FR-071KL") (field (name "Manufacturer") "YAGEO(国巨)"))
      (libsource (lib "easyedapro") (part "SC1206J1500F8ANRH"))
    )
    (comp (ref "R18")
      (value "1kΩ")
      (fields (field (name "Manufacturer Part") "RC0603FR-071KL") (field (name "Manufacturer") "YAGEO(国巨)"))
      (libsource (lib "easyedapro") (part "SC1206J1500F8ANRH"))
    )
    (comp (ref "RN4")
      (value "1kΩ")
      (footprint "easyedapro:RES-ARRAY-SMD_0603-8P-L3.2-W1.6-BL")
      (fields
        (field (name "Manufacturer Part") "4D03WGJ0102T5E")
        (field (name "Manufacturer") "UNI-ROYAL(厚声)")
      )
      (libsource (lib "easyedapro") (part "4D03WGJ0102T5E"))
    )
    (comp (ref "RN5")
      (value "1kΩ")
      (footprint "easyedapro:RES-ARRAY-SMD_0603-8P-L3.2-W1.6-BL")
      (fields
        (field (name "Manufacturer Part") "4D03WGJ0102T5E")
        (field (name "Manufacturer") "UNI-ROYAL(厚声)")
      )
      (libsource (lib "easyedapro") (part "4D03WGJ0102T5E"))
    )
    (comp (ref "RN6")
      (value "1kΩ")
      (footprint "easyedapro:RES-ARRAY-SMD_0603-8P-L3.2-W1.6-BL")
      (fields
        (field (name "Manufacturer Part") "4D03WGJ0102T5E")
        (field (name "Manufacturer") "UNI-ROYAL(厚声)")
      )
      (libsource (lib "easyedapro") (part "4D03WGJ0102T5E"))
    )
    (comp (ref "RN7")
      (value "1kΩ")
      (footprint "easyedapro:RES-ARRAY-SMD_0603-8P-L3.2-W1.6-BL")
      (fields
        (field (name "Manufacturer Part") "4D03WGJ0102T5E")
        (field (name "Manufacturer") "UNI-ROYAL(厚声)")
      )
      (libsource (lib "easyedapro") (part "4D03WGJ0102T5E"))
    )
    (comp (ref "RN8")
      (value "1kΩ")
      (footprint "easyedapro:RES-ARRAY-SMD_0603-8P-L3.2-W1.6-BL")
      (fields
        (field (name "Manufacturer Part") "4D03WGJ0102T5E")
        (field (name "Manufacturer") "UNI-ROYAL(厚声)")
      )
      (libsource (lib "easyedapro") (part "4D03WGJ0102T5E"))
    )
    (comp (ref "RN9")
      (value "1kΩ")
      (footprint "easyedapro:RES-ARRAY-SMD_0603-8P-L3.2-W1.6-BL")
      (fields
        (field (name "Manufacturer Part") "4D03WGJ0102T5E")
        (field (name "Manufacturer") "UNI-ROYAL(厚声)")
      )
      (libsource (lib "easyedapro") (part "4D03WGJ0102T5E"))
    )
    (comp (ref "RN10")
      (value "1kΩ")
      (footprint "easyedapro:RES-ARRAY-SMD_0603-8P-L3.2-W1.6-BL")
      (fields
        (field (name "Manufacturer Part") "4D03WGJ0102T5E")
        (field (name "Manufacturer") "UNI-ROYAL(厚声)")
      )
      (libsource (lib "easyedapro") (part "4D03WGJ0102T5E"))
    )
    (comp (ref "RN11")
      (value "1kΩ")
      (footprint "easyedapro:RES-ARRAY-SMD_0603-8P-L3.2-W1.6-BL")
      (fields
        (field (name "Manufacturer Part") "4D03WGJ0102T5E")
        (field (name "Manufacturer") "UNI-ROYAL(厚声)")
      )
      (libsource (lib "easyedapro") (part "4D03WGJ0102T5E"))
    )
    (comp (ref "H1")
      (value "2.54-2*20")
      (footprint "easyedapro:HDR-TH_40P-P2.54-V-F-R2-C20-S2.54")
      (fields (field (name "Manufacturer") "ZHOURI(洲日)"))
      (libsource (lib "easyedapro") (part "2.54-2*20"))
    )
    (comp (ref "H2")
      (value "2.54-2*5P简牛")
      (footprint "easyedapro:IDC-TH_10P-P2.54_C5665")
      (fields (field (name "Manufacturer") "BOOMELE(博穆精密)"))
      (libsource (lib "easyedapro") (part "HDR-IDC-2.54-2X5P"))
    )
    (comp (ref "H3")
      (value "HX PM2.54-2x6P WC")
      (footprint "easyedapro:HDR-TH_12P-P2.54-H-F-R2-C6-S2.54-W12.7-N")
      (fields (field (name "Manufacturer") "hanxia(韩下)"))
      (libsource (lib "easyedapro") (part "HX PM2.54-2X6P WC"))
    )
    (comp (ref "H4")
      (value "HX PM2.54-2x6P WC")
      (footprint "easyedapro:HDR-TH_12P-P2.54-H-F-R2-C6-S2.54-W12.7-N")
      (fields (field (name "Manufacturer") "hanxia(韩下)"))
      (libsource (lib "easyedapro") (part "HX PM2.54-2X6P WC"))
    )
    (comp (ref "R19")
      (value "1kΩ")
      (fields (field (name "Manufacturer Part") "RC0603FR-071KL") (field (name "Manufacturer") "YAGEO(国巨)"))
      (libsource (lib "easyedapro") (part "SC1206J1500F8ANRH"))
    )
    (comp (ref "R20")
      (value "10kΩ")
      (fields (field (name "Manufacturer Part") "RC0603FR-071KL") (field (name "Manufacturer") "YAGEO(国巨)"))
      (libsource (lib "easyedapro") (part "SC1206J1500F8ANRH"))
    )
    (comp (ref "R21")
      (value "10kΩ")
      (fields (field (name "Manufacturer Part") "RC0603FR-071KL") (field (name "Manufacturer") "YAGEO(国巨)"))
      (libsource (lib "easyedapro") (part "SC1206J1500F8ANRH"))
    )
    (comp (ref "RN12")
      (value "100Ω")
      (footprint "easyedapro:RES-ARRAY-SMD_0603-8P-L3.2-W1.6-BL")
      (fields (field (name "Manufacturer Part") "YC164-FR-07100RL") (field (name "Manufacturer") "YAGEO(国巨)"))
      (libsource (lib "easyedapro") (part "YC164-FR-07100RL"))
    )
    (comp (ref "RN13")
      (value "100Ω")
      (footprint "easyedapro:RES-ARRAY-SMD_0603-8P-L3.2-W1.6-BL")
      (fields (field (name "Manufacturer Part") "YC164-FR-07100RL") (field (name "Manufacturer") "YAGEO(国巨)"))
      (libsource (lib "easyedapro") (part "YC164-FR-07100RL"))
    )
    (comp (ref "RN14")
      (value "100Ω")
      (footprint "easyedapro:RES-ARRAY-SMD_0603-8P-L3.2-W1.6-BL")
      (fields (field (name "Manufacturer Part") "YC164-FR-07100RL") (field (name "Manufacturer") "YAGEO(国巨)"))
      (libsource (lib "easyedapro") (part "YC164-FR-07100RL"))
    )
    (comp (ref "RN15")
      (value "100Ω")
      (footprint "easyedapro:RES-ARRAY-SMD_0603-8P-L3.2-W1.6-BL")
      (fields (field (name "Manufacturer Part") "YC164-FR-07100RL") (field (name "Manufacturer") "YAGEO(国巨)"))
      (libsource (lib "easyedapro") (part "YC164-FR-07100RL"))
    )
  )
  (nets
    (net (code "1") (name "+5V") (class "Default")
      (node (ref "D1") (pin "1") (pinfunction "C_1") (pintype "unspecified"))
      (node (ref "F1") (pin "2") (pinfunction "2_2") (pintype "unspecified"))
      (node (ref "SW10") (pin "2") (pinfunction "2_2") (pintype "unspecified"))
    )
    (net (code "2") (name "3.3V") (class "Default")
      (node (ref "BUZZER1") (pin "1") (pinfunction "+_1") (pintype "unspecified"))
      (node (ref "C17") (pin "2") (pinfunction "2_2") (pintype "unspecified"))
      (node (ref "C18") (pin "2") (pinfunction "2_2") (pintype "input"))
      (node (ref "C19") (pin "2") (pinfunction "2_2") (pintype "input"))
      (node (ref "C20") (pin "2") (pinfunction "2_2") (pintype "input"))
      (node (ref "C21") (pin "2") (pinfunction "2_2") (pintype "input"))
      (node (ref "C22") (pin "2") (pinfunction "2_2") (pintype "input"))
      (node (ref "C23") (pin "2") (pinfunction "2_2") (pintype "input"))
      (node (ref "C24") (pin "2") (pinfunction "2_2") (pintype "input"))
      (node (ref "C25") (pin "2") (pinfunction "2_2") (pintype "input"))
      (node (ref "C26") (pin "2") (pinfunction "2_2") (pintype "input"))
      (node (ref "C27") (pin "2") (pinfunction "2_2") (pintype "input"))
      (node (ref "C28") (pin "2") (pinfunction "2_2") (pintype "input"))
      (node (ref "C29") (pin "2") (pinfunction "2_2") (pintype "input"))
      (node (ref "C3") (pin "2") (pinfunction "2_2") (pintype "unspecified"))
      (node (ref "C30") (pin "2") (pinfunction "2_2") (pintype "input"))
      (node (ref "C31") (pin "2") (pinfunction "2_2") (pintype "input"))
      (node (ref "C32") (pin "2") (pinfunction "2_2") (pintype "input"))
      (node (ref "C33") (pin "2") (pinfunction "2_2") (pintype "input"))
      (node (ref "C34") (pin "2") (pinfunction "2_2") (pintype "input"))
      (node (ref "C35") (pin "2") (pinfunction "2_2") (pintype "input"))
      (node (ref "C36") (pin "2") (pinfunction "2_2") (pintype "input"))
      (node (ref "C37") (pin "2") (pinfunction "2_2") (pintype "input"))
      (node (ref "C38") (pin "2") (pinfunction "2_2") (pintype "input"))
      (node (ref "C39") (pin "2") (pinfunction "2_2") (pintype "input"))
      (node (ref "C4") (pin "2") (pinfunction "2_2") (pintype "unspecified"))
      (node (ref "C40") (pin "2") (pinfunction "2_2") (pintype "input"))
      (node (ref "C41") (pin "2") (pinfunction "2_2") (pintype "input"))
      (node (ref "D2") (pin "1") (pinfunction "C_1") (pintype "input"))
      (node (ref "H1") (pin "1") (pinfunction "1_1") (pintype "unspecified"))
      (node (ref "H1") (pin "13") (pinfunction "13_13") (pintype "unspecified"))
      (node (ref "H1") (pin "14") (pinfunction "14_14") (pintype "unspecified"))
      (node (ref "H1") (pin "2") (pinfunction "2_2") (pintype "unspecified"))
      (node (ref "H1") (pin "37") (pinfunction "37_37") (pintype "unspecified"))
      (node (ref "H1") (pin "38") (pinfunction "38_38") (pintype "unspecified"))
      (node (ref "H1") (pin "5") (pinfunction "5_5") (pintype "unspecified"))
      (node (ref "H1") (pin "6") (pinfunction "6_6") (pintype "unspecified"))
      (node (ref "H2") (pin "4") (pinfunction "4_4") (pintype "input"))
      (node (ref "H3") (pin "11") (pinfunction "11_11") (pintype "unspecified"))
      (node (ref "H3") (pin "12") (pinfunction "12_12") (pintype "unspecified"))
      (node (ref "H4") (pin "11") (pinfunction "11_11") (pintype "unspecified"))
      (node (ref "H4") (pin "12") (pinfunction "12_12") (pintype "unspecified"))
      (node (ref "L2") (pin "1") (pinfunction "1_1") (pintype "unspecified"))
      (node (ref "L3") (pin "1") (pinfunction "1_1") (pintype "unspecified"))
      (node (ref "L4") (pin "1") (pinfunction "1_1") (pintype "unspecified"))
      (node (ref "L5") (pin "1") (pinfunction "1_1") (pintype "unspecified"))
      (node (ref "L6") (pin "2") (pinfunction "2_2") (pintype "unspecified"))
      (node (ref "OSC1") (pin "1") (pinfunction "Tri-state_1") (pintype "unspecified"))
      (node (ref "OSC1") (pin "4") (pinfunction "VDD_4") (pintype "unspecified"))
      (node (ref "R20") (pin "2") (pinfunction "2_2") (pintype "unspecified"))
      (node (ref "R21") (pin "2") (pinfunction "2_2") (pintype "unspecified"))
      (node (ref "R4") (pin "2") (pinfunction "2_2") (pintype "unspecified"))
      (node (ref "R5") (pin "2") (pinfunction "2_2") (pintype "unspecified"))
      (node (ref "R6") (pin "2") (pinfunction "2_2") (pintype "unspecified"))
      (node (ref "R7") (pin "2") (pinfunction "2_2") (pintype "unspecified"))
      (node (ref "SW0") (pin "3") (pinfunction "3_3") (pintype "unspecified"))
      (node (ref "SW1") (pin "3") (pinfunction "3_3") (pintype "unspecified"))
      (node (ref "SW2") (pin "3") (pinfunction "3_3") (pintype "unspecified"))
      (node (ref "SW3") (pin "3") (pinfunction "3_3") (pintype "unspecified"))
      (node (ref "SW4") (pin "3") (pinfunction "3_3") (pintype "unspecified"))
      (node (ref "SW5") (pin "3") (pinfunction "3_3") (pintype "unspecified"))
      (node (ref "SW6") (pin "3") (pinfunction "3_3") (pintype "unspecified"))
      (node (ref "SW7") (pin "3") (pinfunction "3_3") (pintype "unspecified"))
      (node (ref "SW8") (pin "3") (pinfunction "3_3") (pintype "unspecified"))
      (node (ref "SW9") (pin "3") (pinfunction "3_3") (pintype "unspecified"))
      (node (ref "U2") (pin "1") (pinfunction "FB_1") (pintype "unspecified"))
      (node (ref "U3") (pin "1") (pinfunction "VCC_ONE_1") (pintype "unspecified"))
      (node (ref "U3") (pin "102") (pinfunction "VCCIO6_102") (pintype "unspecified"))
      (node (ref "U3") (pin "108") (pinfunction "VCC_ONE_108") (pintype "unspecified"))
      (node (ref "U3") (pin "109") (pinfunction "VCC_ONE_109") (pintype "unspecified"))
      (node (ref "U3") (pin "111") (pinfunction "VCCIO8_111") (pintype "unspecified"))
      (node (ref "U3") (pin "118") (pinfunction "VCC_ONE_118") (pintype "unspecified"))
      (node (ref "U3") (pin "12") (pinfunction "VCCIO1_12") (pintype "unspecified"))
      (node (ref "U3") (pin "120") (pinfunction "IO/CONFIG_SEL_120") (pintype "unspecified"))
      (node (ref "U3") (pin "121") (pinfunction "VCCIO8_121") (pintype "unspecified"))
      (node (ref "U3") (pin "122") (pinfunction "Input_only/nCONFIG_122") (pintype "unspecified"))
      (node (ref "U3") (pin "13") (pinfunction "IO/JTAGEN_13") (pintype "unspecified"))
      (node (ref "U3") (pin "132") (pinfunction "VCC_ONE_132") (pintype "unspecified"))
      (node (ref "U3") (pin "136") (pinfunction "VCCIO8_136") (pintype "unspecified"))
      (node (ref "U3") (pin "142") (pinfunction "VCC_ONE_142") (pintype "unspecified"))
      (node (ref "U3") (pin "144") (pinfunction "VCC_ONE_144") (pintype "unspecified"))
      (node (ref "U3") (pin "22") (pinfunction "VCCIO1_22") (pintype "unspecified"))
      (node (ref "U3") (pin "29") (pinfunction "VCCIO2_29") (pintype "unspecified"))
      (node (ref "U3") (pin "36") (pinfunction "VCC_ONE_36") (pintype "unspecified"))
      (node (ref "U3") (pin "37") (pinfunction "VCC_ONE_37") (pintype "unspecified"))
      (node (ref "U3") (pin "43") (pinfunction "VCCIO3_43") (pintype "unspecified"))
      (node (ref "U3") (pin "56") (pinfunction "VCCIO3_56") (pintype "unspecified"))
      (node (ref "U3") (pin "58") (pinfunction "VCC_ONE_58") (pintype "unspecified"))
      (node (ref "U3") (pin "64") (pinfunction "VCCIO3_64") (pintype "unspecified"))
      (node (ref "U3") (pin "72") (pinfunction "VCC_ONE_72") (pintype "unspecified"))
      (node (ref "U3") (pin "73") (pinfunction "VCC_ONE_73") (pintype "unspecified"))
      (node (ref "U3") (pin "82") (pinfunction "VCCIO5_82") (pintype "unspecified"))
      (node (ref "U3") (pin "93") (pinfunction "VCCIO6_93") (pintype "unspecified"))
    )
    (net (code "3") (name "3.3VA") (class "Default")
      (node (ref "C42") (pin "2") (pinfunction "2_2") (pintype "input"))
      (node (ref "C43") (pin "2") (pinfunction "2_2") (pintype "input"))
      (node (ref "C44") (pin "2") (pinfunction "2_2") (pintype "input"))
      (node (ref "C45") (pin "2") (pinfunction "2_2") (pintype "input"))
      (node (ref "C46") (pin "2") (pinfunction "2_2") (pintype "input"))
      (node (ref "L2") (pin "2") (pinfunction "2_2") (pintype "unspecified"))
      (node (ref "L3") (pin "2") (pinfunction "2_2") (pintype "unspecified"))
      (node (ref "L4") (pin "2") (pinfunction "2_2") (pintype "unspecified"))
      (node (ref "L5") (pin "2") (pinfunction "2_2") (pintype "unspecified"))
      (node (ref "U3") (pin "107") (pinfunction "VCCA3_107") (pintype "unspecified"))
      (node (ref "U3") (pin "2") (pinfunction "VCCA4_2") (pintype "unspecified"))
      (node (ref "U3") (pin "34") (pinfunction "VCCA2_34") (pintype "unspecified"))
      (node (ref "U3") (pin "35") (pinfunction "VCCA1_35") (pintype "unspecified"))
      (node (ref "U3") (pin "71") (pinfunction "VCCA5_71") (pintype "unspecified"))
    )
    (net (code "4") (name "5VF") (class "Default")
      (node (ref "C2") (pin "2") (pinfunction "2_2") (pintype "unspecified"))
      (node (ref "F1") (pin "1") (pinfunction "1_1") (pintype "unspecified"))
      (node (ref "LED10") (pin "1") (pinfunction "+_1") (pintype "unspecified"))
      (node (ref "U2") (pin "2") (pinfunction "EN_2") (pintype "unspecified"))
      (node (ref "U2") (pin "3") (pinfunction "VIN_3") (pintype "unspecified"))
    )
    (net (code "5") (name "BUZZ") (class "Default")
      (node (ref "R12") (pin "2") (pinfunction "2_2") (pintype "unspecified"))
      (node (ref "U3") (pin "100") (pinfunction "IO/DIFFIO_RX_R18n/DIFFOUT_R18n_100") (pintype "unspecified"))
    )
    (net (code "6") (name "CLK") (class "Default")
      (node (ref "R22") (pin "1") (pinfunction "1_1") (pintype "unspecified"))
      (node (ref "U3") (pin "28") (pinfunction "IO/CLK1p/DIFFIO_RX_L16p/DIFFOUT_L16p_28") (pintype "unspecified"))
    )
    (net (code "7") (name "GND") (class "Default")
      (node (ref "C17") (pin "1") (pinfunction "1_1") (pintype "unspecified"))
      (node (ref "C18") (pin "1") (pinfunction "1_1") (pintype "input"))
      (node (ref "C19") (pin "1") (pinfunction "1_1") (pintype "input"))
      (node (ref "C2") (pin "1") (pinfunction "1_1") (pintype "unspecified"))
      (node (ref "C20") (pin "1") (pinfunction "1_1") (pintype "input"))
      (node (ref "C21") (pin "1") (pinfunction "1_1") (pintype "input"))
      (node (ref "C22") (pin "1") (pinfunction "1_1") (pintype "input"))
      (node (ref "C23") (pin "1") (pinfunction "1_1") (pintype "input"))
      (node (ref "C24") (pin "1") (pinfunction "1_1") (pintype "input"))
      (node (ref "C25") (pin "1") (pinfunction "1_1") (pintype "input"))
      (node (ref "C26") (pin "1") (pinfunction "1_1") (pintype "input"))
      (node (ref "C27") (pin "1") (pinfunction "1_1") (pintype "input"))
      (node (ref "C28") (pin "1") (pinfunction "1_1") (pintype "input"))
      (node (ref "C29") (pin "1") (pinfunction "1_1") (pintype "input"))
      (node (ref "C3") (pin "1") (pinfunction "1_1") (pintype "unspecified"))
      (node (ref "C30") (pin "1") (pinfunction "1_1") (pintype "input"))
      (node (ref "C31") (pin "1") (pinfunction "1_1") (pintype "input"))
      (node (ref "C32") (pin "1") (pinfunction "1_1") (pintype "input"))
      (node (ref "C33") (pin "1") (pinfunction "1_1") (pintype "input"))
      (node (ref "C34") (pin "1") (pinfunction "1_1") (pintype "input"))
      (node (ref "C35") (pin "1") (pinfunction "1_1") (pintype "input"))
      (node (ref "C36") (pin "1") (pinfunction "1_1") (pintype "input"))
      (node (ref "C37") (pin "1") (pinfunction "1_1") (pintype "input"))
      (node (ref "C38") (pin "1") (pinfunction "1_1") (pintype "input"))
      (node (ref "C39") (pin "1") (pinfunction "1_1") (pintype "input"))
      (node (ref "C4") (pin "1") (pinfunction "1_1") (pintype "unspecified"))
      (node (ref "C40") (pin "1") (pinfunction "1_1") (pintype "input"))
      (node (ref "C41") (pin "1") (pinfunction "1_1") (pintype "input"))
      (node (ref "C42") (pin "1") (pinfunction "1_1") (pintype "input"))
      (node (ref "C43") (pin "1") (pinfunction "1_1") (pintype "input"))
      (node (ref "C44") (pin "1") (pinfunction "1_1") (pintype "input"))
      (node (ref "C45") (pin "1") (pinfunction "1_1") (pintype "input"))
      (node (ref "C46") (pin "1") (pinfunction "1_1") (pintype "input"))
      (node (ref "D1") (pin "2") (pinfunction "A_2") (pintype "unspecified"))
      (node (ref "H1") (pin "10") (pinfunction "10_10") (pintype "unspecified"))
      (node (ref "H1") (pin "19") (pinfunction "19_19") (pintype "unspecified"))
      (node (ref "H1") (pin "20") (pinfunction "20_20") (pintype "unspecified"))
      (node (ref "H1") (pin "27") (pinfunction "27_27") (pintype "unspecified"))
      (node (ref "H1") (pin "28") (pinfunction "28_28") (pintype "unspecified"))
      (node (ref "H1") (pin "3") (pinfunction "3_3") (pintype "unspecified"))
      (node (ref "H1") (pin "31") (pinfunction "31_31") (pintype "unspecified"))
      (node (ref "H1") (pin "32") (pinfunction "32_32") (pintype "unspecified"))
      (node (ref "H1") (pin "35") (pinfunction "35_35") (pintype "unspecified"))
      (node (ref "H1") (pin "36") (pinfunction "36_36") (pintype "unspecified"))
      (node (ref "H1") (pin "39") (pinfunction "39_39") (pintype "unspecified"))
      (node (ref "H1") (pin "4") (pinfunction "4_4") (pintype "unspecified"))
      (node (ref "H1") (pin "40") (pinfunction "40_40") (pintype "unspecified"))
      (node (ref "H1") (pin "9") (pinfunction "9_9") (pintype "unspecified"))
      (node (ref "H2") (pin "10") (pinfunction "10_10") (pintype "input"))
      (node (ref "H2") (pin "2") (pinfunction "2_2") (pintype "input"))
      (node (ref "H3") (pin "10") (pinfunction "10_10") (pintype "unspecified"))
      (node (ref "H3") (pin "9") (pinfunction "9_9") (pintype "unspecified"))
      (node (ref "H4") (pin "10") (pinfunction "10_10") (pintype "unspecified"))
      (node (ref "H4") (pin "9") (pinfunction "9_9") (pintype "unspecified"))
      (node (ref "HEX0") (pin "1") (pinfunction "COM_1") (pintype "unspecified"))
      (node (ref "HEX0") (pin "6") (pinfunction "COM_6") (pintype "unspecified"))
      (node (ref "HEX1") (pin "1") (pinfunction "COM_1") (pintype "unspecified"))
      (node (ref "HEX1") (pin "6") (pinfunction "COM_6") (pintype "unspecified"))
      (node (ref "HEX2") (pin "1") (pinfunction "COM_1") (pintype "unspecified"))
      (node (ref "HEX2") (pin "6") (pinfunction "COM_6") (pintype "unspecified"))
      (node (ref "HEX3") (pin "1") (pinfunction "COM_1") (pintype "unspecified"))
      (node (ref "HEX3") (pin "6") (pinfunction "COM_6") (pintype "unspecified"))
      (node (ref "KEY0") (pin "4") (pinfunction "D_4") (pintype "unspecified"))
      (node (ref "KEY1") (pin "4") (pinfunction "D_4") (pintype "unspecified"))
      (node (ref "KEY2") (pin "4") (pinfunction "D_4") (pintype "unspecified"))
      (node (ref "KEY3") (pin "4") (pinfunction "D_4") (pintype "unspecified"))
      (node (ref "OSC1") (pin "2") (pinfunction "GND_2") (pintype "unspecified"))
      (node (ref "Q1") (pin "2") (pinfunction "2_2") (pintype "input"))
      (node (ref "R1") (pin "1") (pinfunction "1_1") (pintype "input"))
      (node (ref "R10") (pin "1") (pinfunction "1_1") (pintype "unspecified"))
      (node (ref "R11") (pin "1") (pinfunction "1_1") (pintype "unspecified"))
      (node (ref "R13") (pin "1") (pinfunction "1_1") (pintype "unspecified"))
      (node (ref "R14") (pin "1") (pinfunction "1_1") (pintype "unspecified"))
      (node (ref "R15") (pin "1") (pinfunction "1_1") (pintype "unspecified"))
      (node (ref "R16") (pin "1") (pinfunction "1_1") (pintype "unspecified"))
      (node (ref "R17") (pin "1") (pinfunction "1_1") (pintype "unspecified"))
      (node (ref "R18") (pin "1") (pinfunction "1_1") (pintype "unspecified"))
      (node (ref "R19") (pin "2") (pinfunction "2_2") (pintype "unspecified"))
      (node (ref "R2") (pin "1") (pinfunction "1_1") (pintype "input"))
      (node (ref "R3") (pin "1") (pinfunction "1_1") (pintype "unspecified"))
      (node (ref "R8") (pin "1") (pinfunction "1_1") (pintype "unspecified"))
      (node (ref "R9") (pin "1") (pinfunction "1_1") (pintype "unspecified"))
      (node (ref "SW0") (pin "1") (pinfunction "1_1") (pintype "unspecified"))
      (node (ref "SW1") (pin "1") (pinfunction "1_1") (pintype "unspecified"))
      (node (ref "SW2") (pin "1") (pinfunction "1_1") (pintype "unspecified"))
      (node (ref "SW3") (pin "1") (pinfunction "1_1") (pintype "unspecified"))
      (node (ref "SW4") (pin "1") (pinfunction "1_1") (pintype "unspecified"))
      (node (ref "SW5") (pin "1") (pinfunction "1_1") (pintype "unspecified"))
      (node (ref "SW6") (pin "1") (pinfunction "1_1") (pintype "unspecified"))
      (node (ref "SW7") (pin "1") (pinfunction "1_1") (pintype "unspecified"))
      (node (ref "SW8") (pin "1") (pinfunction "1_1") (pintype "unspecified"))
      (node (ref "SW9") (pin "1") (pinfunction "1_1") (pintype "unspecified"))
      (node (ref "U1") (pin "A12") (pinfunction "GND_A12") (pintype "unspecified"))
      (node (ref "U1") (pin "B12") (pinfunction "GND_B12") (pintype "unspecified"))
      (node (ref "U2") (pin "4") (pinfunction "GND_4") (pintype "unspecified"))
      (node (ref "U3") (pin "104") (pinfunction "GND_104") (pintype "unspecified"))
      (node (ref "U3") (pin "11") (pinfunction "GND_11") (pintype "unspecified"))
      (node (ref "U3") (pin "110") (pinfunction "GND_110") (pintype "unspecified"))
      (node (ref "U3") (pin "119") (pinfunction "GND_119") (pintype "unspecified"))
      (node (ref "U3") (pin "133") (pinfunction "GND_133") (pintype "unspecified"))
      (node (ref "U3") (pin "143") (pinfunction "GND_143") (pintype "unspecified"))
      (node (ref "U3") (pin "145") (pinfunction "EP_145") (pintype "unspecified"))
      (node (ref "U3") (pin "20") (pinfunction "GND_20") (pintype "unspecified"))
      (node (ref "U3") (pin "30") (pinfunction "GND_30") (pintype "unspecified"))
      (node (ref "U3") (pin "38") (pinfunction "GND_38") (pintype "unspecified"))
      (node (ref "U3") (pin "45") (pinfunction "GND_45") (pintype "unspecified"))
      (node (ref "U3") (pin "57") (pinfunction "GND_57") (pintype "unspecified"))
      (node (ref "U3") (pin "66") (pinfunction "GND_66") (pintype "unspecified"))
      (node (ref "U3") (pin "83") (pinfunction "GND_83") (pintype "unspecified"))
      (node (ref "U3") (pin "96") (pinfunction "GND_96") (pintype "unspecified"))
    )
    (net (code "8") (name "HEX_0_A") (class "Default")
      (node (ref "RN11") (pin "8") (pinfunction "8_8") (pintype "input"))
      (node (ref "U3") (pin "55") (pinfunction "IO/VREFB3N0_55") (pintype "unspecified"))
    )
    (net (code "9") (name "HEX_0_B") (class "Default")
      (node (ref "RN11") (pin "7") (pinfunction "7_7") (pintype "input"))
      (node (ref "U3") (pin "54") (pinfunction "IO/DIFFIO_TX_RX_B7p/DIFFOUT_B7p_54") (pintype "unspecified"))
    )
    (net (code "10") (name "HEX_0_C") (class "Default")
      (node (ref "RN11") (pin "6") (pinfunction "6_6") (pintype "input"))
      (node (ref "U3") (pin "53") (pinfunction "IO/DIFFIO_RX_B8p/DIFFOUT_B8p_53") (pintype "unspecified"))
    )
    (net (code "11") (name "HEX_0_D") (class "Default")
      (node (ref "RN10") (pin "8") (pinfunction "8_8") (pintype "input"))
      (node (ref "U3") (pin "51") (pinfunction "IO/DIFFIO_RX_B8n/DIFFOUT_B8n_51") (pintype "unspecified"))
    )
    (net (code "12") (name "HEX_0_DP") (class "Default")
      (node (ref "RN11") (pin "5") (pinfunction "5_5") (pintype "input"))
      (node (ref "U3") (pin "52") (pinfunction "IO/DIFFIO_TX_RX_B7n/DIFFOUT_B7n_52") (pintype "unspecified"))
    )
    (net (code "13") (name "HEX_0_E") (class "Default")
      (node (ref "RN10") (pin "7") (pinfunction "7_7") (pintype "input"))
      (node (ref "U3") (pin "50") (pinfunction "IO/DIFFIO_TX_RX_B5p/DIFFOUT_B5p_50") (pintype "unspecified"))
    )
    (net (code "14") (name "HEX_0_F") (class "Default")
      (node (ref "RN10") (pin "5") (pinfunction "5_5") (pintype "input"))
      (node (ref "U3") (pin "48") (pinfunction "IO/DIFFIO_TX_RX_B5n/DIFFOUT_B5n_48") (pintype "unspecified"))
    )
    (net (code "15") (name "HEX_0_G") (class "Default")
      (node (ref "RN10") (pin "6") (pinfunction "6_6") (pintype "input"))
      (node (ref "U3") (pin "49") (pinfunction "IO/DIFFIO_RX_B6p/DIFFOUT_B6p_49") (pintype "unspecified"))
    )
    (net (code "16") (name "HEX_1_A") (class "Default")
      (node (ref "RN9") (pin "8") (pinfunction "8_8") (pintype "input"))
      (node (ref "U3") (pin "47") (pinfunction "IO/DIFFIO_RX_B6n/DIFFOUT_B6n_47") (pintype "unspecified"))
    )
    (net (code "17") (name "HEX_1_B") (class "Default")
      (node (ref "RN9") (pin "7") (pinfunction "7_7") (pintype "input"))
      (node (ref "U3") (pin "46") (pinfunction "IO/DIFFIO_TX_RX_B3p/DIFFOUT_B3p_46") (pintype "unspecified"))
    )
    (net (code "18") (name "HEX_1_C") (class "Default")
      (node (ref "RN9") (pin "6") (pinfunction "6_6") (pintype "input"))
      (node (ref "U3") (pin "44") (pinfunction "IO/DIFFIO_TX_RX_B3n/DIFFOUT_B3n_44") (pintype "unspecified"))
    )
    (net (code "19") (name "HEX_1_D") (class "Default")
      (node (ref "RN8") (pin "8") (pinfunction "8_8") (pintype "input"))
      (node (ref "U3") (pin "41") (pinfunction "IO/DIFFIO_RX_B2p/DIFFOUT_B2p_41") (pintype "unspecified"))
    )
    (net (code "20") (name "HEX_1_DP") (class "Default")
      (node (ref "RN9") (pin "5") (pinfunction "5_5") (pintype "input"))
      (node (ref "U3") (pin "42") (pinfunction "IO/DIFFIO_TX_RX_B1p/DIFFOUT_B1p_42") (pintype "unspecified"))
    )
    (net (code "21") (name "HEX_1_E") (class "Default")
      (node (ref "RN8") (pin "7") (pinfunction "7_7") (pintype "input"))
      (node (ref "U3") (pin "40") (pinfunction "IO/DIFFIO_TX_RX_B1n/DIFFOUT_B1n_40") (pintype "unspecified"))
    )
    (net (code "22") (name "HEX_1_F") (class "Default")
      (node (ref "RN8") (pin "5") (pinfunction "5_5") (pintype "input"))
      (node (ref "U3") (pin "33") (pinfunction "IO/PLL_L_CLKOUTp/DIFFIO_RX_L19p/DIFFOUT_L19p_33") (pintype "unspecified"))
    )
    (net (code "23") (name "HEX_1_G") (class "Default")
      (node (ref "RN8") (pin "6") (pinfunction "6_6") (pintype "input"))
      (node (ref "U3") (pin "39") (pinfunction "IO/DIFFIO_RX_B2n/DIFFOUT_B2n_39") (pintype "unspecified"))
    )
    (net (code "24") (name "HEX_2_A") (class "Default")
      (node (ref "RN7") (pin "8") (pinfunction "8_8") (pintype "input"))
      (node (ref "U3") (pin "32") (pinfunction "IO/PLL_L_CLKOUTn/DIFFIO_RX_L19n/DIFFOUT_L19n_32") (pintype "unspecified"))
    )
    (net (code "25") (name "HEX_2_B") (class "Default")
      (node (ref "RN7") (pin "7") (pinfunction "7_7") (pintype "input"))
      (node (ref "U3") (pin "31") (pinfunction "IO/VREFB2N0_31") (pintype "unspecified"))
    )
    (net (code "26") (name "HEX_2_C") (class "Default")
      (node (ref "RN7") (pin "6") (pinfunction "6_6") (pintype "input"))
      (node (ref "U3") (pin "27") (pinfunction "IO/CLK1n/DIFFIO_RX_L16n/DIFFOUT_L16n_27") (pintype "unspecified"))
    )
    (net (code "27") (name "HEX_2_D") (class "Default")
      (node (ref "RN6") (pin "8") (pinfunction "8_8") (pintype "input"))
      (node (ref "U3") (pin "25") (pinfunction "IO/CLK0n/DIFFIO_RX_L14n/DIFFOUT_L14n_25") (pintype "unspecified"))
    )
    (net (code "28") (name "HEX_2_DP") (class "Default")
      (node (ref "RN7") (pin "5") (pinfunction "5_5") (pintype "input"))
      (node (ref "U3") (pin "26") (pinfunction "IO/CLK0p/DIFFIO_RX_L14p/DIFFOUT_L14p_26") (pintype "unspecified"))
    )
    (net (code "29") (name "HEX_2_E") (class "Default")
      (node (ref "RN6") (pin "7") (pinfunction "7_7") (pintype "input"))
      (node (ref "U3") (pin "24") (pinfunction "IO/DIFFIO_RX_L12p/DIFFOUT_L12p_24") (pintype "unspecified"))
    )
    (net (code "30") (name "HEX_2_F") (class "Default")
      (node (ref "RN6") (pin "5") (pinfunction "5_5") (pintype "input"))
      (node (ref "U3") (pin "21") (pinfunction "IO/DIFFIO_RX_L10p/DIFFOUT_L10p_21") (pintype "unspecified"))
    )
    (net (code "31") (name "HEX_2_G") (class "Default")
      (node (ref "RN6") (pin "6") (pinfunction "6_6") (pintype "input"))
      (node (ref "U3") (pin "23") (pinfunction "IO/DIFFIO_RX_L12n/DIFFOUT_L12n_23") (pintype "unspecified"))
    )
    (net (code "32") (name "HEX_3_A") (class "Default")
      (node (ref "RN5") (pin "8") (pinfunction "8_8") (pintype "input"))
      (node (ref "U3") (pin "10") (pinfunction "IO/DIFFIO_RX_L3p/DIFFOUT_L3p_10") (pintype "unspecified"))
    )
    (net (code "33") (name "HEX_3_B") (class "Default")
      (node (ref "RN5") (pin "7") (pinfunction "7_7") (pintype "input"))
      (node (ref "U3") (pin "9") (pinfunction "IO/DIFFIO_RX_L4p/DIFFOUT_L4p_9") (pintype "unspecified"))
    )
    (net (code "34") (name "HEX_3_C") (class "Default")
      (node (ref "RN5") (pin "6") (pinfunction "6_6") (pintype "input"))
      (node (ref "U3") (pin "8") (pinfunction "IO/DIFFIO_RX_L3n/DIFFOUT_L3n_8") (pintype "unspecified"))
    )
    (net (code "35") (name "HEX_3_D") (class "Default")
      (node (ref "RN4") (pin "8") (pinfunction "8_8") (pintype "input"))
      (node (ref "U3") (pin "6") (pinfunction "IO/DIFFIO_RX_L1p/DIFFOUT_L1p_6") (pintype "unspecified"))
    )
    (net (code "36") (name "HEX_3_DP") (class "Default")
      (node (ref "RN5") (pin "5") (pinfunction "5_5") (pintype "input"))
      (node (ref "U3") (pin "7") (pinfunction "IO/DIFFIO_RX_L4n/DIFFOUT_L4n_7") (pintype "unspecified"))
    )
    (net (code "37") (name "HEX_3_E") (class "Default")
      (node (ref "RN4") (pin "7") (pinfunction "7_7") (pintype "input"))
      (node (ref "U3") (pin "5") (pinfunction "IO/DIFFIO_RX_L2p/DIFFOUT_L2p_5") (pintype "unspecified"))
    )
    (net (code "38") (name "HEX_3_F") (class "Default")
      (node (ref "RN4") (pin "5") (pinfunction "5_5") (pintype "input"))
      (node (ref "U3") (pin "3") (pinfunction "IO/DIFFIO_RX_L2n/DIFFOUT_L2n_3") (pintype "unspecified"))
    )
    (net (code "39") (name "HEX_3_G") (class "Default")
      (node (ref "RN4") (pin "6") (pinfunction "6_6") (pintype "input"))
      (node (ref "U3") (pin "4") (pinfunction "IO/DIFFIO_RX_L1n/DIFFOUT_L1n_4") (pintype "unspecified"))
    )
    (net (code "40") (name "KEY0") (class "Default")
      (node (ref "KEY0") (pin "2") (pinfunction "B_2") (pintype "unspecified"))
      (node (ref "R7") (pin "1") (pinfunction "1_1") (pintype "unspecified"))
      (node (ref "U3") (pin "77") (pinfunction "IO_77") (pintype "unspecified"))
    )
    (net (code "41") (name "KEY1") (class "Default")
      (node (ref "KEY1") (pin "2") (pinfunction "B_2") (pintype "unspecified"))
      (node (ref "R6") (pin "1") (pinfunction "1_1") (pintype "unspecified"))
      (node (ref "U3") (pin "76") (pinfunction "IO/DIFFIO_RX_R2n/DIFFOUT_R2n_76") (pintype "unspecified"))
    )
    (net (code "42") (name "KEY2") (class "Default")
      (node (ref "KEY2") (pin "2") (pinfunction "B_2") (pintype "unspecified"))
      (node (ref "R5") (pin "1") (pinfunction "1_1") (pintype "unspecified"))
      (node (ref "U3") (pin "75") (pinfunction "IO/DIFFIO_RX_R1p/DIFFOUT_R1p_75") (pintype "unspecified"))
    )
    (net (code "43") (name "KEY3") (class "Default")
      (node (ref "KEY3") (pin "2") (pinfunction "B_2") (pintype "unspecified"))
      (node (ref "R4") (pin "1") (pinfunction "1_1") (pintype "unspecified"))
      (node (ref "U3") (pin "74") (pinfunction "IO/DIFFIO_RX_R2p/DIFFOUT_R2p_74") (pintype "unspecified"))
    )
    (net (code "44") (name "LED0") (class "Default")
      (node (ref "LED0") (pin "1") (pinfunction "+_1") (pintype "unspecified"))
      (node (ref "U3") (pin "70") (pinfunction "IO/DIFFIO_RX_B17p/DIFFOUT_B17p_70") (pintype "unspecified"))
    )
    (net (code "45") (name "LED1") (class "Default")
      (node (ref "LED1") (pin "1") (pinfunction "+_1") (pintype "unspecified"))
      (node (ref "U3") (pin "69") (pinfunction "IO/DIFFIO_TX_RX_B16p/DIFFOUT_B16p_69") (pintype "unspecified"))
    )
    (net (code "46") (name "LED2") (class "Default")
      (node (ref "LED2") (pin "1") (pinfunction "+_1") (pintype "unspecified"))
      (node (ref "U3") (pin "68") (pinfunction "IO/DIFFIO_RX_B17n/DIFFOUT_B17n_68") (pintype "unspecified"))
    )
    (net (code "47") (name "LED3") (class "Default")
      (node (ref "LED3") (pin "1") (pinfunction "+_1") (pintype "unspecified"))
      (node (ref "U3") (pin "67") (pinfunction "IO/DIFFIO_TX_RX_B16n/DIFFOUT_B16n_67") (pintype "unspecified"))
    )
    (net (code "48") (name "LED4") (class "Default")
      (node (ref "LED4") (pin "1") (pinfunction "+_1") (pintype "unspecified"))
      (node (ref "U3") (pin "65") (pinfunction "IO/DIFFIO_TX_RX_B14p/DIFFOUT_B14p_65") (pintype "unspecified"))
    )
    (net (code "49") (name "LED5") (class "Default")
      (node (ref "LED5") (pin "1") (pinfunction "+_1") (pintype "unspecified"))
      (node (ref "U3") (pin "63") (pinfunction "IO/DIFFIO_TX_RX_B14n/DIFFOUT_B14n_63") (pintype "unspecified"))
    )
    (net (code "50") (name "LED6") (class "Default")
      (node (ref "LED6") (pin "1") (pinfunction "+_1") (pintype "unspecified"))
      (node (ref "U3") (pin "62") (pinfunction "IO/DIFFIO_RX_B13p/DIFFOUT_B13p_62") (pintype "unspecified"))
    )
    (net (code "51") (name "LED7") (class "Default")
      (node (ref "LED7") (pin "1") (pinfunction "+_1") (pintype "unspecified"))
      (node (ref "U3") (pin "61") (pinfunction "IO/DIFFIO_TX_RX_B12p/DIFFOUT_B12p_61") (pintype "unspecified"))
    )
    (net (code "52") (name "LED8") (class "Default")
      (node (ref "LED8") (pin "1") (pinfunction "+_1") (pintype "unspecified"))
      (node (ref "U3") (pin "60") (pinfunction "IO/DIFFIO_RX_B13n/DIFFOUT_B13n_60") (pintype "unspecified"))
    )
    (net (code "53") (name "LED9") (class "Default")
      (node (ref "LED9") (pin "1") (pinfunction "+_1") (pintype "unspecified"))
      (node (ref "U3") (pin "59") (pinfunction "IO/DIFFIO_TX_RX_B12n/DIFFOUT_B12n_59") (pintype "unspecified"))
    )
    (net (code "54") (name "Net-(BUZZER1--)") (class "Default")
      (node (ref "BUZZER1") (pin "2") (pinfunction "-_2") (pintype "unspecified"))
      (node (ref "D2") (pin "2") (pinfunction "A_2") (pintype "input"))
      (node (ref "Q1") (pin "3") (pinfunction "3_3") (pintype "input"))
    )
    (net (code "55") (name "Net-(H3-Pad1)") (class "Default")
      (node (ref "H3") (pin "1") (pinfunction "1_1") (pintype "unspecified"))
      (node (ref "RN13") (pin "1") (pinfunction "1_1") (pintype "input"))
    )
    (net (code "56") (name "Net-(H3-Pad2)") (class "Default")
      (node (ref "H3") (pin "2") (pinfunction "2_2") (pintype "unspecified"))
      (node (ref "RN13") (pin "2") (pinfunction "2_2") (pintype "input"))
    )
    (net (code "57") (name "Net-(H3-Pad3)") (class "Default")
      (node (ref "H3") (pin "3") (pinfunction "3_3") (pintype "unspecified"))
      (node (ref "RN13") (pin "3") (pinfunction "3_3") (pintype "input"))
    )
    (net (code "58") (name "Net-(H3-Pad4)") (class "Default")
      (node (ref "H3") (pin "4") (pinfunction "4_4") (pintype "unspecified"))
      (node (ref "RN13") (pin "4") (pinfunction "4_4") (pintype "input"))
    )
    (net (code "59") (name "Net-(H3-Pad5)") (class "Default")
      (node (ref "H3") (pin "5") (pinfunction "5_5") (pintype "unspecified"))
      (node (ref "RN12") (pin "1") (pinfunction "1_1") (pintype "input"))
    )
    (net (code "60") (name "Net-(H3-Pad6)") (class "Default")
      (node (ref "H3") (pin "6") (pinfunction "6_6") (pintype "unspecified"))
      (node (ref "RN12") (pin "2") (pinfunction "2_2") (pintype "input"))
    )
    (net (code "61") (name "Net-(H3-Pad7)") (class "Default")
      (node (ref "H3") (pin "7") (pinfunction "7_7") (pintype "unspecified"))
      (node (ref "RN12") (pin "3") (pinfunction "3_3") (pintype "input"))
    )
    (net (code "62") (name "Net-(H3-Pad8)") (class "Default")
      (node (ref "H3") (pin "8") (pinfunction "8_8") (pintype "unspecified"))
      (node (ref "RN12") (pin "4") (pinfunction "4_4") (pintype "input"))
    )
    (net (code "63") (name "Net-(H4-Pad1)") (class "Default")
      (node (ref "H4") (pin "1") (pinfunction "1_1") (pintype "unspecified"))
      (node (ref "RN15") (pin "1") (pinfunction "1_1") (pintype "input"))
    )
    (net (code "64") (name "Net-(H4-Pad2)") (class "Default")
      (node (ref "H4") (pin "2") (pinfunction "2_2") (pintype "unspecified"))
      (node (ref "RN15") (pin "2") (pinfunction "2_2") (pintype "input"))
    )
    (net (code "65") (name "Net-(H4-Pad3)") (class "Default")
      (node (ref "H4") (pin "3") (pinfunction "3_3") (pintype "unspecified"))
      (node (ref "RN15") (pin "3") (pinfunction "3_3") (pintype "input"))
    )
    (net (code "66") (name "Net-(H4-Pad4)") (class "Default")
      (node (ref "H4") (pin "4") (pinfunction "4_4") (pintype "unspecified"))
      (node (ref "RN15") (pin "4") (pinfunction "4_4") (pintype "input"))
    )
    (net (code "67") (name "Net-(H4-Pad5)") (class "Default")
      (node (ref "H4") (pin "5") (pinfunction "5_5") (pintype "unspecified"))
      (node (ref "RN14") (pin "1") (pinfunction "1_1") (pintype "input"))
    )
    (net (code "68") (name "Net-(H4-Pad6)") (class "Default")
      (node (ref "H4") (pin "6") (pinfunction "6_6") (pintype "unspecified"))
      (node (ref "RN14") (pin "2") (pinfunction "2_2") (pintype "input"))
    )
    (net (code "69") (name "Net-(H4-Pad7)") (class "Default")
      (node (ref "H4") (pin "7") (pinfunction "7_7") (pintype "unspecified"))
      (node (ref "RN14") (pin "3") (pinfunction "3_3") (pintype "input"))
    )
    (net (code "70") (name "Net-(H4-Pad8)") (class "Default")
      (node (ref "H4") (pin "8") (pinfunction "8_8") (pintype "unspecified"))
      (node (ref "RN14") (pin "4") (pinfunction "4_4") (pintype "input"))
    )
    (net (code "71") (name "Net-(HEX0-A)") (class "Default")
      (node (ref "HEX0") (pin "10") (pinfunction "A_10") (pintype "unspecified"))
      (node (ref "RN11") (pin "1") (pinfunction "1_1") (pintype "input"))
    )
    (net (code "72") (name "Net-(HEX0-B)") (class "Default")
      (node (ref "HEX0") (pin "9") (pinfunction "B_9") (pintype "unspecified"))
      (node (ref "RN11") (pin "2") (pinfunction "2_2") (pintype "input"))
    )
    (net (code "73") (name "Net-(HEX0-C)") (class "Default")
      (node (ref "HEX0") (pin "8") (pinfunction "C_8") (pintype "unspecified"))
      (node (ref "RN11") (pin "3") (pinfunction "3_3") (pintype "input"))
    )
    (net (code "74") (name "Net-(HEX0-D)") (class "Default")
      (node (ref "HEX0") (pin "5") (pinfunction "D_5") (pintype "unspecified"))
      (node (ref "RN10") (pin "1") (pinfunction "1_1") (pintype "input"))
    )
    (net (code "75") (name "Net-(HEX0-DP)") (class "Default")
      (node (ref "HEX0") (pin "7") (pinfunction "DP_7") (pintype "unspecified"))
      (node (ref "RN11") (pin "4") (pinfunction "4_4") (pintype "input"))
    )
    (net (code "76") (name "Net-(HEX0-E)") (class "Default")
      (node (ref "HEX0") (pin "4") (pinfunction "E_4") (pintype "unspecified"))
      (node (ref "RN10") (pin "2") (pinfunction "2_2") (pintype "input"))
    )
    (net (code "77") (name "Net-(HEX0-F)") (class "Default")
      (node (ref "HEX0") (pin "2") (pinfunction "F_2") (pintype "unspecified"))
      (node (ref "RN10") (pin "4") (pinfunction "4_4") (pintype "input"))
    )
    (net (code "78") (name "Net-(HEX0-G)") (class "Default")
      (node (ref "HEX0") (pin "3") (pinfunction "G_3") (pintype "unspecified"))
      (node (ref "RN10") (pin "3") (pinfunction "3_3") (pintype "input"))
    )
    (net (code "79") (name "Net-(HEX1-A)") (class "Default")
      (node (ref "HEX1") (pin "10") (pinfunction "A_10") (pintype "unspecified"))
      (node (ref "RN9") (pin "1") (pinfunction "1_1") (pintype "input"))
    )
    (net (code "80") (name "Net-(HEX1-B)") (class "Default")
      (node (ref "HEX1") (pin "9") (pinfunction "B_9") (pintype "unspecified"))
      (node (ref "RN9") (pin "2") (pinfunction "2_2") (pintype "input"))
    )
    (net (code "81") (name "Net-(HEX1-C)") (class "Default")
      (node (ref "HEX1") (pin "8") (pinfunction "C_8") (pintype "unspecified"))
      (node (ref "RN9") (pin "3") (pinfunction "3_3") (pintype "input"))
    )
    (net (code "82") (name "Net-(HEX1-D)") (class "Default")
      (node (ref "HEX1") (pin "5") (pinfunction "D_5") (pintype "unspecified"))
      (node (ref "RN8") (pin "1") (pinfunction "1_1") (pintype "input"))
    )
    (net (code "83") (name "Net-(HEX1-DP)") (class "Default")
      (node (ref "HEX1") (pin "7") (pinfunction "DP_7") (pintype "unspecified"))
      (node (ref "RN9") (pin "4") (pinfunction "4_4") (pintype "input"))
    )
    (net (code "84") (name "Net-(HEX1-E)") (class "Default")
      (node (ref "HEX1") (pin "4") (pinfunction "E_4") (pintype "unspecified"))
      (node (ref "RN8") (pin "2") (pinfunction "2_2") (pintype "input"))
    )
    (net (code "85") (name "Net-(HEX1-F)") (class "Default")
      (node (ref "HEX1") (pin "2") (pinfunction "F_2") (pintype "unspecified"))
      (node (ref "RN8") (pin "4") (pinfunction "4_4") (pintype "input"))
    )
    (net (code "86") (name "Net-(HEX1-G)") (class "Default")
      (node (ref "HEX1") (pin "3") (pinfunction "G_3") (pintype "unspecified"))
      (node (ref "RN8") (pin "3") (pinfunction "3_3") (pintype "input"))
    )
    (net (code "87") (name "Net-(HEX2-A)") (class "Default")
      (node (ref "HEX2") (pin "10") (pinfunction "A_10") (pintype "unspecified"))
      (node (ref "RN7") (pin "1") (pinfunction "1_1") (pintype "input"))
    )
    (net (code "88") (name "Net-(HEX2-B)") (class "Default")
      (node (ref "HEX2") (pin "9") (pinfunction "B_9") (pintype "unspecified"))
      (node (ref "RN7") (pin "2") (pinfunction "2_2") (pintype "input"))
    )
    (net (code "89") (name "Net-(HEX2-C)") (class "Default")
      (node (ref "HEX2") (pin "8") (pinfunction "C_8") (pintype "unspecified"))
      (node (ref "RN7") (pin "3") (pinfunction "3_3") (pintype "input"))
    )
    (net (code "90") (name "Net-(HEX2-D)") (class "Default")
      (node (ref "HEX2") (pin "5") (pinfunction "D_5") (pintype "unspecified"))
      (node (ref "RN6") (pin "1") (pinfunction "1_1") (pintype "input"))
    )
    (net (code "91") (name "Net-(HEX2-DP)") (class "Default")
      (node (ref "HEX2") (pin "7") (pinfunction "DP_7") (pintype "unspecified"))
      (node (ref "RN7") (pin "4") (pinfunction "4_4") (pintype "input"))
    )
    (net (code "92") (name "Net-(HEX2-E)") (class "Default")
      (node (ref "HEX2") (pin "4") (pinfunction "E_4") (pintype "unspecified"))
      (node (ref "RN6") (pin "2") (pinfunction "2_2") (pintype "input"))
    )
    (net (code "93") (name "Net-(HEX2-F)") (class "Default")
      (node (ref "HEX2") (pin "2") (pinfunction "F_2") (pintype "unspecified"))
      (node (ref "RN6") (pin "4") (pinfunction "4_4") (pintype "input"))
    )
    (net (code "94") (name "Net-(HEX2-G)") (class "Default")
      (node (ref "HEX2") (pin "3") (pinfunction "G_3") (pintype "unspecified"))
      (node (ref "RN6") (pin "3") (pinfunction "3_3") (pintype "input"))
    )
    (net (code "95") (name "Net-(HEX3-A)") (class "Default")
      (node (ref "HEX3") (pin "10") (pinfunction "A_10") (pintype "unspecified"))
      (node (ref "RN5") (pin "1") (pinfunction "1_1") (pintype "input"))
    )
    (net (code "96") (name "Net-(HEX3-B)") (class "Default")
      (node (ref "HEX3") (pin "9") (pinfunction "B_9") (pintype "unspecified"))
      (node (ref "RN5") (pin "2") (pinfunction "2_2") (pintype "input"))
    )
    (net (code "97") (name "Net-(HEX3-C)") (class "Default")
      (node (ref "HEX3") (pin "8") (pinfunction "C_8") (pintype "unspecified"))
      (node (ref "RN5") (pin "3") (pinfunction "3_3") (pintype "input"))
    )
    (net (code "98") (name "Net-(HEX3-D)") (class "Default")
      (node (ref "HEX3") (pin "5") (pinfunction "D_5") (pintype "unspecified"))
      (node (ref "RN4") (pin "1") (pinfunction "1_1") (pintype "input"))
    )
    (net (code "99") (name "Net-(HEX3-DP)") (class "Default")
      (node (ref "HEX3") (pin "7") (pinfunction "DP_7") (pintype "unspecified"))
      (node (ref "RN5") (pin "4") (pinfunction "4_4") (pintype "input"))
    )
    (net (code "100") (name "Net-(HEX3-E)") (class "Default")
      (node (ref "HEX3") (pin "4") (pinfunction "E_4") (pintype "unspecified"))
      (node (ref "RN4") (pin "2") (pinfunction "2_2") (pintype "input"))
    )
    (net (code "101") (name "Net-(HEX3-F)") (class "Default")
      (node (ref "HEX3") (pin "2") (pinfunction "F_2") (pintype "unspecified"))
      (node (ref "RN4") (pin "4") (pinfunction "4_4") (pintype "input"))
    )
    (net (code "102") (name "Net-(HEX3-G)") (class "Default")
      (node (ref "HEX3") (pin "3") (pinfunction "G_3") (pintype "unspecified"))
      (node (ref "RN4") (pin "3") (pinfunction "3_3") (pintype "input"))
    )
    (net (code "103") (name "Net-(LED0--)") (class "Default")
      (node (ref "LED0") (pin "2") (pinfunction "-_2") (pintype "unspecified"))
      (node (ref "R8") (pin "2") (pinfunction "2_2") (pintype "unspecified"))
    )
    (net (code "104") (name "Net-(LED1--)") (class "Default")
      (node (ref "LED1") (pin "2") (pinfunction "-_2") (pintype "unspecified"))
      (node (ref "R13") (pin "2") (pinfunction "2_2") (pintype "unspecified"))
    )
    (net (code "105") (name "Net-(LED2--)") (class "Default")
      (node (ref "LED2") (pin "2") (pinfunction "-_2") (pintype "unspecified"))
      (node (ref "R9") (pin "2") (pinfunction "2_2") (pintype "unspecified"))
    )
    (net (code "106") (name "Net-(LED3--)") (class "Default")
      (node (ref "LED3") (pin "2") (pinfunction "-_2") (pintype "unspecified"))
      (node (ref "R14") (pin "2") (pinfunction "2_2") (pintype "unspecified"))
    )
    (net (code "107") (name "Net-(LED4--)") (class "Default")
      (node (ref "LED4") (pin "2") (pinfunction "-_2") (pintype "unspecified"))
      (node (ref "R10") (pin "2") (pinfunction "2_2") (pintype "unspecified"))
    )
    (net (code "108") (name "Net-(LED5--)") (class "Default")
      (node (ref "LED5") (pin "2") (pinfunction "-_2") (pintype "unspecified"))
      (node (ref "R15") (pin "2") (pinfunction "2_2") (pintype "unspecified"))
    )
    (net (code "109") (name "Net-(LED6--)") (class "Default")
      (node (ref "LED6") (pin "2") (pinfunction "-_2") (pintype "unspecified"))
      (node (ref "R11") (pin "2") (pinfunction "2_2") (pintype "unspecified"))
    )
    (net (code "110") (name "Net-(LED7--)") (class "Default")
      (node (ref "LED7") (pin "2") (pinfunction "-_2") (pintype "unspecified"))
      (node (ref "R16") (pin "2") (pinfunction "2_2") (pintype "unspecified"))
    )
    (net (code "111") (name "Net-(LED8--)") (class "Default")
      (node (ref "LED8") (pin "2") (pinfunction "-_2") (pintype "unspecified"))
      (node (ref "R17") (pin "2") (pinfunction "2_2") (pintype "unspecified"))
    )
    (net (code "112") (name "Net-(LED9--)") (class "Default")
      (node (ref "LED9") (pin "2") (pinfunction "-_2") (pintype "unspecified"))
      (node (ref "R18") (pin "2") (pinfunction "2_2") (pintype "unspecified"))
    )
    (net (code "113") (name "Net-(LED10--)") (class "Default")
      (node (ref "LED10") (pin "2") (pinfunction "-_2") (pintype "unspecified"))
      (node (ref "R3") (pin "2") (pinfunction "2_2") (pintype "unspecified"))
    )
    (net (code "114") (name "Net-(OSC1-OUT)") (class "Default")
      (node (ref "OSC1") (pin "3") (pinfunction "OUT_3") (pintype "unspecified"))
      (node (ref "R22") (pin "2") (pinfunction "2_2") (pintype "unspecified"))
    )
    (net (code "115") (name "Net-(Q1-Pad1)") (class "Default")
      (node (ref "Q1") (pin "1") (pinfunction "1_1") (pintype "input"))
      (node (ref "R12") (pin "1") (pinfunction "1_1") (pintype "unspecified"))
    )
    (net (code "116") (name "Net-(RN1-Pad1)") (class "Default")
      (node (ref "RN1") (pin "1") (pinfunction "1_1") (pintype "input"))
      (node (ref "SW0") (pin "2") (pinfunction "2_2") (pintype "unspecified"))
    )
    (net (code "117") (name "Net-(RN1-Pad2)") (class "Default")
      (node (ref "RN1") (pin "2") (pinfunction "2_2") (pintype "input"))
      (node (ref "SW1") (pin "2") (pinfunction "2_2") (pintype "unspecified"))
    )
    (net (code "118") (name "Net-(RN1-Pad3)") (class "Default")
      (node (ref "RN1") (pin "3") (pinfunction "3_3") (pintype "input"))
      (node (ref "SW2") (pin "2") (pinfunction "2_2") (pintype "unspecified"))
    )
    (net (code "119") (name "Net-(RN1-Pad4)") (class "Default")
      (node (ref "RN1") (pin "4") (pinfunction "4_4") (pintype "input"))
      (node (ref "SW3") (pin "2") (pinfunction "2_2") (pintype "unspecified"))
    )
    (net (code "120") (name "Net-(RN2-Pad1)") (class "Default")
      (node (ref "RN2") (pin "1") (pinfunction "1_1") (pintype "input"))
      (node (ref "SW4") (pin "2") (pinfunction "2_2") (pintype "unspecified"))
    )
    (net (code "121") (name "Net-(RN2-Pad2)") (class "Default")
      (node (ref "RN2") (pin "2") (pinfunction "2_2") (pintype "input"))
      (node (ref "SW5") (pin "2") (pinfunction "2_2") (pintype "unspecified"))
    )
    (net (code "122") (name "Net-(RN2-Pad3)") (class "Default")
      (node (ref "RN2") (pin "3") (pinfunction "3_3") (pintype "input"))
      (node (ref "SW6") (pin "2") (pinfunction "2_2") (pintype "unspecified"))
    )
    (net (code "123") (name "Net-(RN2-Pad4)") (class "Default")
      (node (ref "RN2") (pin "4") (pinfunction "4_4") (pintype "input"))
      (node (ref "SW7") (pin "2") (pinfunction "2_2") (pintype "unspecified"))
    )
    (net (code "124") (name "Net-(RN3-Pad1)") (class "Default")
      (node (ref "RN3") (pin "1") (pinfunction "1_1") (pintype "input"))
      (node (ref "SW8") (pin "2") (pinfunction "2_2") (pintype "unspecified"))
    )
    (net (code "125") (name "Net-(RN3-Pad2)") (class "Default")
      (node (ref "RN3") (pin "2") (pinfunction "2_2") (pintype "input"))
      (node (ref "SW9") (pin "2") (pinfunction "2_2") (pintype "unspecified"))
    )
    (net (code "126") (name "Net-(U1-CC1)") (class "Default")
      (node (ref "R1") (pin "2") (pinfunction "2_2") (pintype "input"))
      (node (ref "U1") (pin "A5") (pinfunction "CC1_A5") (pintype "unspecified"))
    )
    (net (code "127") (name "Net-(U1-CC2)") (class "Default")
      (node (ref "R2") (pin "2") (pinfunction "2_2") (pintype "input"))
      (node (ref "U1") (pin "B5") (pinfunction "CC2_B5") (pintype "unspecified"))
    )
    (net (code "128") (name "Net-(U2-BST)") (class "Default")
      (node (ref "C1") (pin "1") (pinfunction "1_1") (pintype "input"))
      (node (ref "U2") (pin "6") (pinfunction "BST_6") (pintype "unspecified"))
    )
    (net (code "129") (name "Net-(U2-SW)") (class "Default")
      (node (ref "C1") (pin "2") (pinfunction "2_2") (pintype "input"))
      (node (ref "L6") (pin "1") (pinfunction "1_1") (pintype "unspecified"))
      (node (ref "U2") (pin "5") (pinfunction "SW_5") (pintype "unspecified"))
    )
    (net (code "130") (name "P1_IO1") (class "Default")
      (node (ref "RN13") (pin "8") (pinfunction "8_8") (pintype "input"))
      (node (ref "U3") (pin "115") (pinfunction "IO/DEV_OE/DIFFIO_RX_T5p/DIFFOUT_T5p_115") (pintype "unspecified"))
    )
    (net (code "131") (name "P1_IO2") (class "Default")
      (node (ref "RN13") (pin "7") (pinfunction "7_7") (pintype "input"))
      (node (ref "U3") (pin "114") (pinfunction "IO/VREFB8N0_114") (pintype "unspecified"))
    )
    (net (code "132") (name "P1_IO3") (class "Default")
      (node (ref "RN13") (pin "6") (pinfunction "6_6") (pintype "input"))
      (node (ref "U3") (pin "113") (pinfunction "IO/DEV_CLRn/DIFFIO_RX_T3n/DIFFOUT_T3n_113") (pintype "unspecified"))
    )
    (net (code "133") (name "P1_IO4") (class "Default")
      (node (ref "RN13") (pin "5") (pinfunction "5_5") (pintype "input"))
      (node (ref "U3") (pin "112") (pinfunction "IO/DIFFIO_RX_T3p/DIFFOUT_T3p_112") (pintype "unspecified"))
    )
    (net (code "134") (name "P1_IO5") (class "Default")
      (node (ref "RN12") (pin "8") (pinfunction "8_8") (pintype "input"))
      (node (ref "U3") (pin "106") (pinfunction "IO/DIFFIO_RX_R23n/DIFFOUT_R23n_106") (pintype "unspecified"))
    )
    (net (code "135") (name "P1_IO6") (class "Default")
      (node (ref "RN12") (pin "7") (pinfunction "7_7") (pintype "input"))
      (node (ref "U3") (pin "105") (pinfunction "IO/DIFFIO_RX_R23p/DIFFOUT_R23p_105") (pintype "unspecified"))
    )
    (net (code "136") (name "P1_IO7") (class "Default")
      (node (ref "RN12") (pin "6") (pinfunction "6_6") (pintype "input"))
      (node (ref "U3") (pin "103") (pinfunction "IO/DIFFIO_RX_R21n/DIFFOUT_R21n_103") (pintype "unspecified"))
    )
    (net (code "137") (name "P1_IO8") (class "Default")
      (node (ref "RN12") (pin "5") (pinfunction "5_5") (pintype "input"))
      (node (ref "U3") (pin "101") (pinfunction "IO/DIFFIO_RX_R21p/DIFFOUT_R21p_101") (pintype "unspecified"))
    )
    (net (code "138") (name "P2_IO1") (class "Default")
      (node (ref "RN15") (pin "8") (pinfunction "8_8") (pintype "input"))
      (node (ref "U3") (pin "99") (pinfunction "IO/DIFFIO_RX_R17n/DIFFOUT_R17n_99") (pintype "unspecified"))
    )
    (net (code "139") (name "P2_IO2") (class "Default")
      (node (ref "RN15") (pin "7") (pinfunction "7_7") (pintype "input"))
      (node (ref "U3") (pin "98") (pinfunction "IO/DIFFIO_RX_R18p/DIFFOUT_R18p_98") (pintype "unspecified"))
    )
    (net (code "140") (name "P2_IO3") (class "Default")
      (node (ref "RN15") (pin "6") (pinfunction "6_6") (pintype "input"))
      (node (ref "U3") (pin "97") (pinfunction "IO/DIFFIO_RX_R17p/DIFFOUT_R17p_97") (pintype "unspecified"))
    )
    (net (code "141") (name "P2_IO4") (class "Default")
      (node (ref "RN15") (pin "5") (pinfunction "5_5") (pintype "input"))
      (node (ref "U3") (pin "95") (pinfunction "IO/DPCLK2/DIFFIO_RX_R16n/DIFFOUT_R16n_95") (pintype "unspecified"))
    )
    (net (code "142") (name "P2_IO5") (class "Default")
      (node (ref "RN14") (pin "8") (pinfunction "8_8") (pintype "input"))
      (node (ref "U3") (pin "94") (pinfunction "IO/DPCLK3/DIFFIO_RX_R16p/DIFFOUT_R16p_94") (pintype "unspecified"))
    )
    (net (code "143") (name "P2_IO6") (class "Default")
      (node (ref "RN14") (pin "7") (pinfunction "7_7") (pintype "input"))
      (node (ref "U3") (pin "92") (pinfunction "IO/VREFB6N0_92") (pintype "unspecified"))
    )
    (net (code "144") (name "P2_IO7") (class "Default")
      (node (ref "RN14") (pin "6") (pinfunction "6_6") (pintype "input"))
      (node (ref "U3") (pin "91") (pinfunction "IO/CLK3n/DIFFIO_RX_R12n/DIFFOUT_R12n_91") (pintype "unspecified"))
    )
    (net (code "145") (name "P2_IO8") (class "Default")
      (node (ref "RN14") (pin "5") (pinfunction "5_5") (pintype "input"))
      (node (ref "U3") (pin "90") (pinfunction "IO/CLK3p/DIFFIO_RX_R12p/DIFFOUT_R12p_90") (pintype "unspecified"))
    )
    (net (code "146") (name "PIN_0") (class "Default")
      (node (ref "H1") (pin "34") (pinfunction "34_34") (pintype "unspecified"))
      (node (ref "U3") (pin "116") (pinfunction "IO_116") (pintype "unspecified"))
    )
    (net (code "147") (name "PIN_1") (class "Default")
      (node (ref "H1") (pin "33") (pinfunction "33_33") (pintype "unspecified"))
      (node (ref "U3") (pin "117") (pinfunction "IO/DIFFIO_RX_T5n/DIFFOUT_T5n_117") (pintype "unspecified"))
    )
    (net (code "148") (name "PIN_2") (class "Default")
      (node (ref "H1") (pin "30") (pinfunction "30_30") (pintype "unspecified"))
      (node (ref "U3") (pin "123") (pinfunction "IO/DIFFIO_RX_T8p/DIFFOUT_T8p_123") (pintype "unspecified"))
    )
    (net (code "149") (name "PIN_3") (class "Default")
      (node (ref "H1") (pin "29") (pinfunction "29_29") (pintype "unspecified"))
      (node (ref "U3") (pin "124") (pinfunction "IO/DIFFIO_RX_T7p/DIFFOUT_T7p_124") (pintype "unspecified"))
    )
    (net (code "150") (name "PIN_4") (class "Default")
      (node (ref "H1") (pin "26") (pinfunction "26_26") (pintype "unspecified"))
      (node (ref "U3") (pin "125") (pinfunction "IO/DIFFIO_RX_T8n/DIFFOUT_T8n_125") (pintype "unspecified"))
    )
    (net (code "151") (name "PIN_5") (class "Default")
      (node (ref "H1") (pin "25") (pinfunction "25_25") (pintype "unspecified"))
      (node (ref "U3") (pin "126") (pinfunction "IO/DIFFIO_RX_T7n/DIFFOUT_T7n_126") (pintype "unspecified"))
    )
    (net (code "152") (name "PIN_6") (class "Default")
      (node (ref "H1") (pin "24") (pinfunction "24_24") (pintype "unspecified"))
      (node (ref "U3") (pin "127") (pinfunction "IO/DIFFIO_RX_T10p/DIFFOUT_T10p_127") (pintype "unspecified"))
    )
    (net (code "153") (name "PIN_7") (class "Default")
      (node (ref "H1") (pin "23") (pinfunction "23_23") (pintype "unspecified"))
      (node (ref "U3") (pin "128") (pinfunction "IO/DIFFIO_RX_T9p/DIFFOUT_T9p_128") (pintype "unspecified"))
    )
    (net (code "154") (name "PIN_8") (class "Default")
      (node (ref "H1") (pin "22") (pinfunction "22_22") (pintype "unspecified"))
      (node (ref "U3") (pin "129") (pinfunction "IO/DIFFIO_RX_T10n/DIFFOUT_T10n_129") (pintype "unspecified"))
    )
    (net (code "155") (name "PIN_9") (class "Default")
      (node (ref "H1") (pin "21") (pinfunction "21_21") (pintype "unspecified"))
      (node (ref "U3") (pin "130") (pinfunction "IO/CRC_ERROR/DIFFIO_RX_T9n/DIFFOUT_T9n_130") (pintype "unspecified"))
    )
    (net (code "156") (name "PIN_10") (class "Default")
      (node (ref "H1") (pin "18") (pinfunction "18_18") (pintype "unspecified"))
      (node (ref "U3") (pin "131") (pinfunction "IO/nSTATUS/DIFFIO_RX_T11p/DIFFOUT_T11p_131") (pintype "unspecified"))
    )
    (net (code "157") (name "PIN_11") (class "Default")
      (node (ref "H1") (pin "17") (pinfunction "17_17") (pintype "unspecified"))
      (node (ref "U3") (pin "134") (pinfunction "IO/DIFFIO_RX_T12p/DIFFOUT_T12p_134") (pintype "unspecified"))
    )
    (net (code "158") (name "PIN_12") (class "Default")
      (node (ref "H1") (pin "16") (pinfunction "16_16") (pintype "unspecified"))
      (node (ref "U3") (pin "135") (pinfunction "IO/CONF_DONE/DIFFIO_RX_T11n/DIFFOUT_T11n_135") (pintype "unspecified"))
    )
    (net (code "159") (name "PIN_13") (class "Default")
      (node (ref "H1") (pin "15") (pinfunction "15_15") (pintype "unspecified"))
      (node (ref "U3") (pin "137") (pinfunction "IO/DIFFIO_RX_T12n/DIFFOUT_T12n_137") (pintype "unspecified"))
    )
    (net (code "160") (name "PIN_14") (class "Default")
      (node (ref "H1") (pin "12") (pinfunction "12_12") (pintype "unspecified"))
      (node (ref "U3") (pin "138") (pinfunction "IO/DIFFIO_RX_T13p/DIFFOUT_T13p_138") (pintype "unspecified"))
    )
    (net (code "161") (name "PIN_15") (class "Default")
      (node (ref "H1") (pin "11") (pinfunction "11_11") (pintype "unspecified"))
      (node (ref "U3") (pin "139") (pinfunction "IO/DIFFIO_RX_T14p/DIFFOUT_T14p_139") (pintype "unspecified"))
    )
    (net (code "162") (name "PIN_16") (class "Default")
      (node (ref "H1") (pin "8") (pinfunction "8_8") (pintype "unspecified"))
      (node (ref "U3") (pin "140") (pinfunction "IO/DIFFIO_RX_T13n/DIFFOUT_T13n_140") (pintype "unspecified"))
    )
    (net (code "163") (name "PIN_17") (class "Default")
      (node (ref "H1") (pin "7") (pinfunction "7_7") (pintype "unspecified"))
      (node (ref "U3") (pin "141") (pinfunction "IO/DIFFIO_RX_T14n/DIFFOUT_T14n_141") (pintype "unspecified"))
    )
    (net (code "164") (name "SW0") (class "Default")
      (node (ref "RN1") (pin "8") (pinfunction "8_8") (pintype "input"))
      (node (ref "U3") (pin "89") (pinfunction "IO/CLK2n/DIFFIO_RX_R10n/DIFFOUT_R10n_89") (pintype "unspecified"))
    )
    (net (code "165") (name "SW1") (class "Default")
      (node (ref "RN1") (pin "7") (pinfunction "7_7") (pintype "input"))
      (node (ref "U3") (pin "88") (pinfunction "IO/CLK2p/DIFFIO_RX_R10p/DIFFOUT_R10p_88") (pintype "unspecified"))
    )
    (net (code "166") (name "SW2") (class "Default")
      (node (ref "RN1") (pin "6") (pinfunction "6_6") (pintype "input"))
      (node (ref "U3") (pin "87") (pinfunction "IO/DIFFIO_RX_R6n/DIFFOUT_R6n_87") (pintype "unspecified"))
    )
    (net (code "167") (name "SW3") (class "Default")
      (node (ref "RN1") (pin "5") (pinfunction "5_5") (pintype "input"))
      (node (ref "U3") (pin "86") (pinfunction "IO/DIFFIO_RX_R7n/DIFFOUT_R7n_86") (pintype "unspecified"))
    )
    (net (code "168") (name "SW4") (class "Default")
      (node (ref "RN2") (pin "8") (pinfunction "8_8") (pintype "input"))
      (node (ref "U3") (pin "85") (pinfunction "IO/DIFFIO_RX_R6p/DIFFOUT_R6p_85") (pintype "unspecified"))
    )
    (net (code "169") (name "SW5") (class "Default")
      (node (ref "RN2") (pin "7") (pinfunction "7_7") (pintype "input"))
      (node (ref "U3") (pin "84") (pinfunction "IO/DIFFIO_RX_R7p/DIFFOUT_R7p_84") (pintype "unspecified"))
    )
    (net (code "170") (name "SW6") (class "Default")
      (node (ref "RN2") (pin "6") (pinfunction "6_6") (pintype "input"))
      (node (ref "U3") (pin "81") (pinfunction "IO/DIFFIO_RX_R3n/DIFFOUT_R3n_81") (pintype "unspecified"))
    )
    (net (code "171") (name "SW7") (class "Default")
      (node (ref "RN2") (pin "5") (pinfunction "5_5") (pintype "input"))
      (node (ref "U3") (pin "80") (pinfunction "IO/VREFB5N0_80") (pintype "unspecified"))
    )
    (net (code "172") (name "SW8") (class "Default")
      (node (ref "RN3") (pin "8") (pinfunction "8_8") (pintype "input"))
      (node (ref "U3") (pin "79") (pinfunction "IO/DIFFIO_RX_R3p/DIFFOUT_R3p_79") (pintype "unspecified"))
    )
    (net (code "173") (name "SW9") (class "Default")
      (node (ref "RN3") (pin "7") (pinfunction "7_7") (pintype "input"))
      (node (ref "U3") (pin "78") (pinfunction "IO/DIFFIO_RX_R1n/DIFFOUT_R1n_78") (pintype "unspecified"))
    )
    (net (code "174") (name "TCK") (class "Default")
      (node (ref "H2") (pin "1") (pinfunction "1_1") (pintype "input"))
      (node (ref "R19") (pin "1") (pinfunction "1_1") (pintype "unspecified"))
      (node (ref "U3") (pin "16") (pinfunction "IO/TCK/DIFFIO_RX_L7p/DIFFOUT_L7p_16") (pintype "unspecified"))
    )
    (net (code "175") (name "TDI") (class "Default")
      (node (ref "H2") (pin "9") (pinfunction "9_9") (pintype "input"))
      (node (ref "R21") (pin "1") (pinfunction "1_1") (pintype "unspecified"))
      (node (ref "U3") (pin "17") (pinfunction "IO/TDI/DIFFIO_RX_L8n/DIFFOUT_L8n_17") (pintype "unspecified"))
    )
    (net (code "176") (name "TDO") (class "Default")
      (node (ref "H2") (pin "3") (pinfunction "3_3") (pintype "input"))
      (node (ref "U3") (pin "18") (pinfunction "IO/TDO/DIFFIO_RX_L8p/DIFFOUT_L8p_18") (pintype "unspecified"))
    )
    (net (code "177") (name "TMS") (class "Default")
      (node (ref "H2") (pin "5") (pinfunction "5_5") (pintype "input"))
      (node (ref "R20") (pin "1") (pinfunction "1_1") (pintype "unspecified"))
      (node (ref "U3") (pin "15") (pinfunction "IO/TMS/DIFFIO_RX_L7n/DIFFOUT_L7n_15") (pintype "unspecified"))
    )
    (net (code "178") (name "VCC") (class "Default")
      (node (ref "SW10") (pin "3") (pinfunction "3_3") (pintype "unspecified"))
      (node (ref "U1") (pin "A9") (pinfunction "VBUS_A9") (pintype "unspecified"))
      (node (ref "U1") (pin "B9") (pinfunction "VBUS_B9") (pintype "unspecified"))
    )
    (net (code "179") (name "unconnected-(BUZZER1-Pad3)") (class "Default")
      (node (ref "BUZZER1") (pin "3") (pinfunction "3_3") (pintype "unspecified+no_connect"))
    )
    (net (code "180") (name "unconnected-(BUZZER1-Pad4)") (class "Default")
      (node (ref "BUZZER1") (pin "4") (pinfunction "4_4") (pintype "unspecified+no_connect"))
    )
    (net (code "181") (name "unconnected-(H2-Pad6)") (class "Default")
      (node (ref "H2") (pin "6") (pinfunction "6_6") (pintype "input+no_connect"))
    )
    (net (code "182") (name "unconnected-(H2-Pad7)") (class "Default")
      (node (ref "H2") (pin "7") (pinfunction "7_7") (pintype "input+no_connect"))
    )
    (net (code "183") (name "unconnected-(H2-Pad8)") (class "Default")
      (node (ref "H2") (pin "8") (pinfunction "8_8") (pintype "input+no_connect"))
    )
    (net (code "184") (name "unconnected-(KEY0-A-Pad1)") (class "Default")
      (node (ref "KEY0") (pin "1") (pinfunction "A_1") (pintype "unspecified"))
    )
    (net (code "185") (name "unconnected-(KEY0-C-Pad3)") (class "Default")
      (node (ref "KEY0") (pin "3") (pinfunction "C_3") (pintype "unspecified"))
    )
    (net (code "186") (name "unconnected-(KEY1-A-Pad1)") (class "Default")
      (node (ref "KEY1") (pin "1") (pinfunction "A_1") (pintype "unspecified"))
    )
    (net (code "187") (name "unconnected-(KEY1-C-Pad3)") (class "Default")
      (node (ref "KEY1") (pin "3") (pinfunction "C_3") (pintype "unspecified"))
    )
    (net (code "188") (name "unconnected-(KEY2-A-Pad1)") (class "Default")
      (node (ref "KEY2") (pin "1") (pinfunction "A_1") (pintype "unspecified"))
    )
    (net (code "189") (name "unconnected-(KEY2-C-Pad3)") (class "Default")
      (node (ref "KEY2") (pin "3") (pinfunction "C_3") (pintype "unspecified"))
    )
    (net (code "190") (name "unconnected-(KEY3-A-Pad1)") (class "Default")
      (node (ref "KEY3") (pin "1") (pinfunction "A_1") (pintype "unspecified"))
    )
    (net (code "191") (name "unconnected-(KEY3-C-Pad3)") (class "Default")
      (node (ref "KEY3") (pin "3") (pinfunction "C_3") (pintype "unspecified"))
    )
    (net (code "192") (name "unconnected-(RN3-Pad3)") (class "Default")
      (node (ref "RN3") (pin "3") (pinfunction "3_3") (pintype "input"))
    )
    (net (code "193") (name "unconnected-(RN3-Pad4)") (class "Default")
      (node (ref "RN3") (pin "4") (pinfunction "4_4") (pintype "input"))
    )
    (net (code "194") (name "unconnected-(RN3-Pad5)") (class "Default")
      (node (ref "RN3") (pin "5") (pinfunction "5_5") (pintype "input"))
    )
    (net (code "195") (name "unconnected-(RN3-Pad6)") (class "Default")
      (node (ref "RN3") (pin "6") (pinfunction "6_6") (pintype "input"))
    )
    (net (code "196") (name "unconnected-(SW0-Pad4)") (class "Default")
      (node (ref "SW0") (pin "4") (pinfunction "4_4") (pintype "unspecified+no_connect"))
    )
    (net (code "197") (name "unconnected-(SW0-Pad5)") (class "Default")
      (node (ref "SW0") (pin "5") (pinfunction "5_5") (pintype "unspecified+no_connect"))
    )
    (net (code "198") (name "unconnected-(SW1-Pad4)") (class "Default")
      (node (ref "SW1") (pin "4") (pinfunction "4_4") (pintype "unspecified+no_connect"))
    )
    (net (code "199") (name "unconnected-(SW1-Pad5)") (class "Default")
      (node (ref "SW1") (pin "5") (pinfunction "5_5") (pintype "unspecified+no_connect"))
    )
    (net (code "200") (name "unconnected-(SW2-Pad4)") (class "Default")
      (node (ref "SW2") (pin "4") (pinfunction "4_4") (pintype "unspecified+no_connect"))
    )
    (net (code "201") (name "unconnected-(SW2-Pad5)") (class "Default")
      (node (ref "SW2") (pin "5") (pinfunction "5_5") (pintype "unspecified+no_connect"))
    )
    (net (code "202") (name "unconnected-(SW3-Pad4)") (class "Default")
      (node (ref "SW3") (pin "4") (pinfunction "4_4") (pintype "unspecified+no_connect"))
    )
    (net (code "203") (name "unconnected-(SW3-Pad5)") (class "Default")
      (node (ref "SW3") (pin "5") (pinfunction "5_5") (pintype "unspecified+no_connect"))
    )
    (net (code "204") (name "unconnected-(SW4-Pad4)") (class "Default")
      (node (ref "SW4") (pin "4") (pinfunction "4_4") (pintype "unspecified+no_connect"))
    )
    (net (code "205") (name "unconnected-(SW4-Pad5)") (class "Default")
      (node (ref "SW4") (pin "5") (pinfunction "5_5") (pintype "unspecified+no_connect"))
    )
    (net (code "206") (name "unconnected-(SW5-Pad4)") (class "Default")
      (node (ref "SW5") (pin "4") (pinfunction "4_4") (pintype "unspecified+no_connect"))
    )
    (net (code "207") (name "unconnected-(SW5-Pad5)") (class "Default")
      (node (ref "SW5") (pin "5") (pinfunction "5_5") (pintype "unspecified+no_connect"))
    )
    (net (code "208") (name "unconnected-(SW6-Pad4)") (class "Default")
      (node (ref "SW6") (pin "4") (pinfunction "4_4") (pintype "unspecified+no_connect"))
    )
    (net (code "209") (name "unconnected-(SW6-Pad5)") (class "Default")
      (node (ref "SW6") (pin "5") (pinfunction "5_5") (pintype "unspecified+no_connect"))
    )
    (net (code "210") (name "unconnected-(SW7-Pad4)") (class "Default")
      (node (ref "SW7") (pin "4") (pinfunction "4_4") (pintype "unspecified+no_connect"))
    )
    (net (code "211") (name "unconnected-(SW7-Pad5)") (class "Default")
      (node (ref "SW7") (pin "5") (pinfunction "5_5") (pintype "unspecified+no_connect"))
    )
    (net (code "212") (name "unconnected-(SW8-Pad4)") (class "Default")
      (node (ref "SW8") (pin "4") (pinfunction "4_4") (pintype "unspecified+no_connect"))
    )
    (net (code "213") (name "unconnected-(SW8-Pad5)") (class "Default")
      (node (ref "SW8") (pin "5") (pinfunction "5_5") (pintype "unspecified+no_connect"))
    )
    (net (code "214") (name "unconnected-(SW9-Pad4)") (class "Default")
      (node (ref "SW9") (pin "4") (pinfunction "4_4") (pintype "unspecified+no_connect"))
    )
    (net (code "215") (name "unconnected-(SW9-Pad5)") (class "Default")
      (node (ref "SW9") (pin "5") (pinfunction "5_5") (pintype "unspecified+no_connect"))
    )
    (net (code "216") (name "unconnected-(SW10-Pad1)") (class "Default")
      (node (ref "SW10") (pin "1") (pinfunction "1_1") (pintype "unspecified+no_connect"))
    )
    (net (code "217") (name "unconnected-(SW10-Pad4)") (class "Default")
      (node (ref "SW10") (pin "4") (pinfunction "4_4") (pintype "unspecified+no_connect"))
    )
    (net (code "218") (name "unconnected-(SW10-Pad5)") (class "Default")
      (node (ref "SW10") (pin "5") (pinfunction "5_5") (pintype "unspecified+no_connect"))
    )
    (net (code "219") (name "unconnected-(SW10-Pad6)") (class "Default")
      (node (ref "SW10") (pin "6") (pinfunction "6_6") (pintype "unspecified+no_connect"))
    )
    (net (code "220") (name "unconnected-(SW10-Pad7)") (class "Default")
      (node (ref "SW10") (pin "7") (pinfunction "7_7") (pintype "unspecified+no_connect"))
    )
    (net (code "221") (name "unconnected-(U1-EH-Pad7)") (class "Default")
      (node (ref "U1") (pin "7") (pinfunction "EH_7") (pintype "unspecified+no_connect"))
    )
    (net (code "222") (name "unconnected-(U3A-IO{slash}DIFFIO_RX_L10n{slash}DIFFOUT_L10n-Pad19)") (class "Default")
      (node (ref "U3") (pin "19") (pinfunction "IO/DIFFIO_RX_L10n/DIFFOUT_L10n_19") (pintype "unspecified"))
    )
    (net (code "223") (name "unconnected-(U3A-IO{slash}VREFB1N0-Pad14)") (class "Default")
      (node (ref "U3") (pin "14") (pinfunction "IO/VREFB1N0_14") (pintype "unspecified"))
    )
  )
)
